# testboard_chip1.net
KiCad netlist of a schematic drawn in Altium Designer
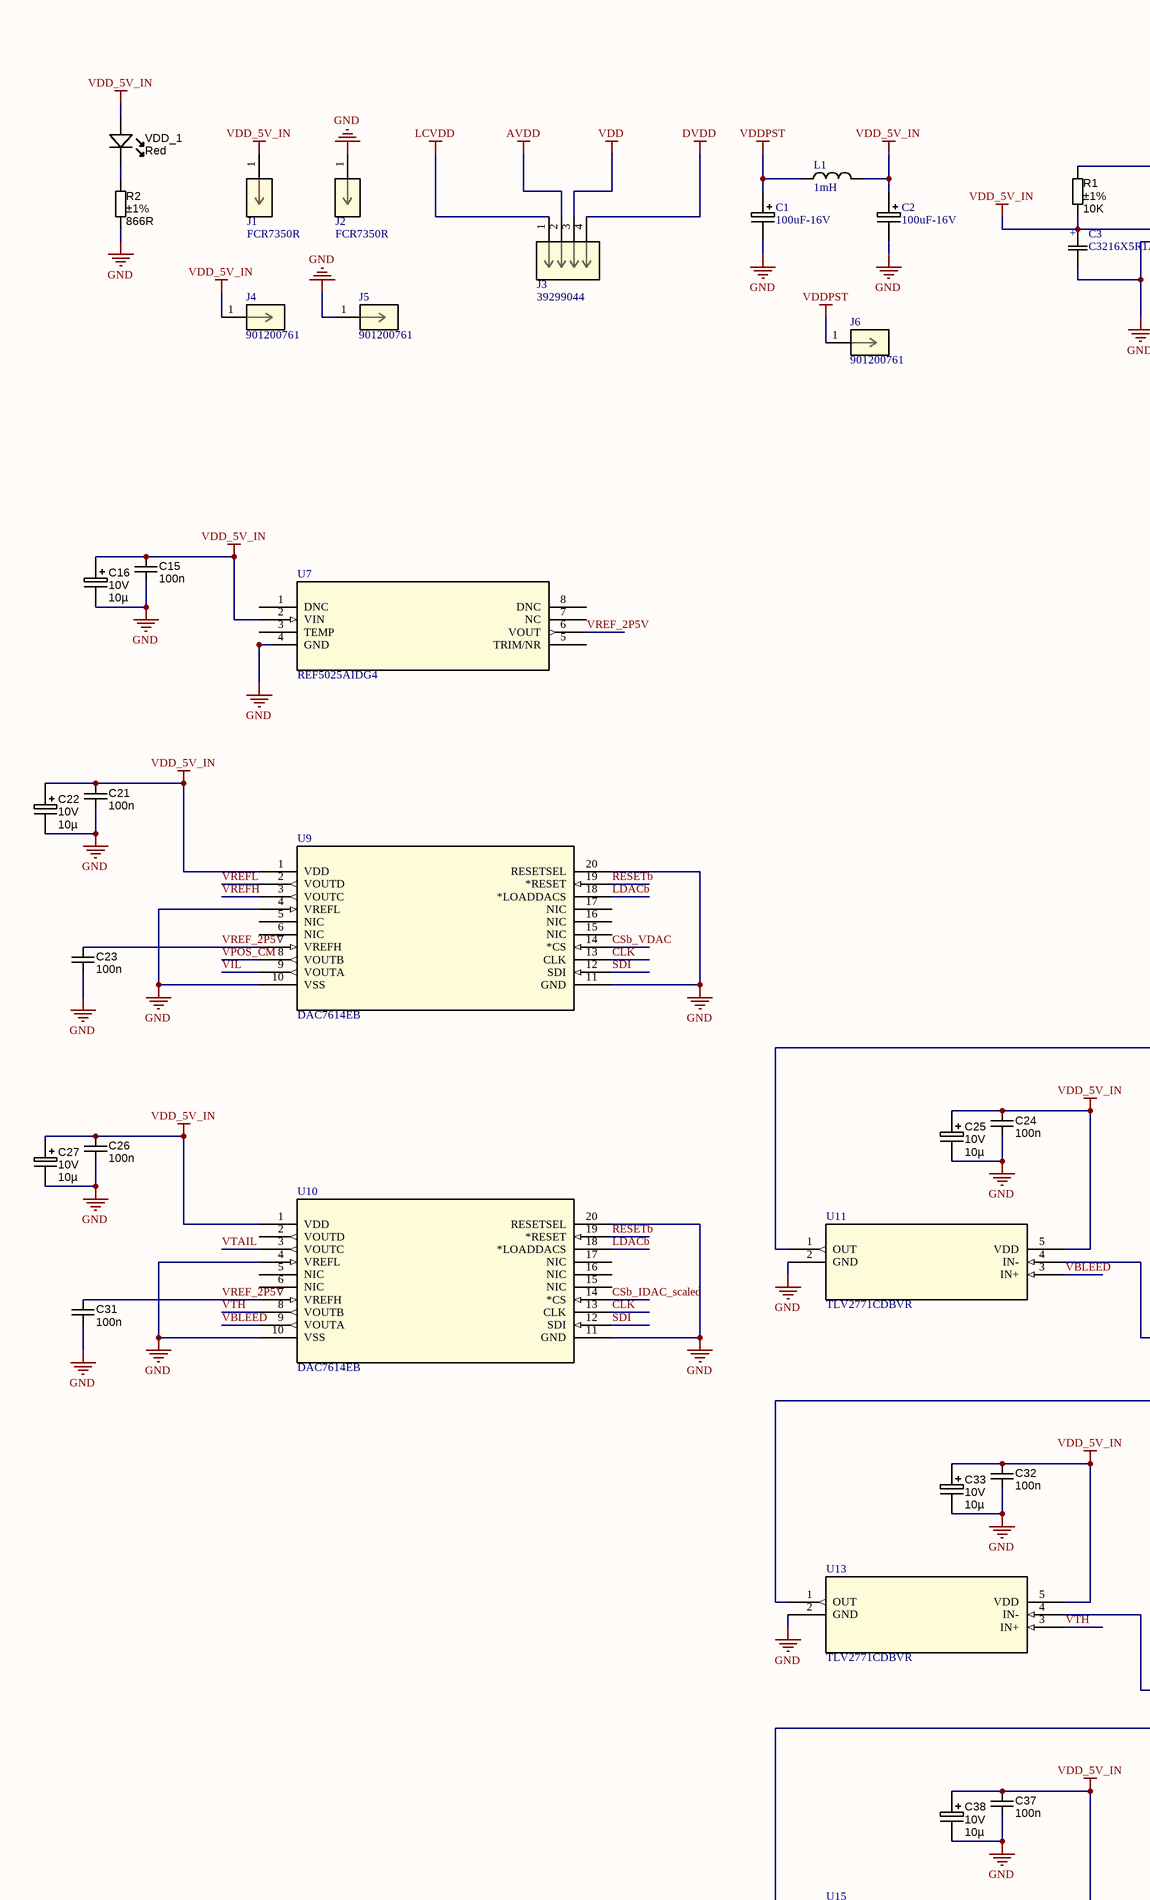
[diagram p0: testboard_chip1.SchDoc, top left]
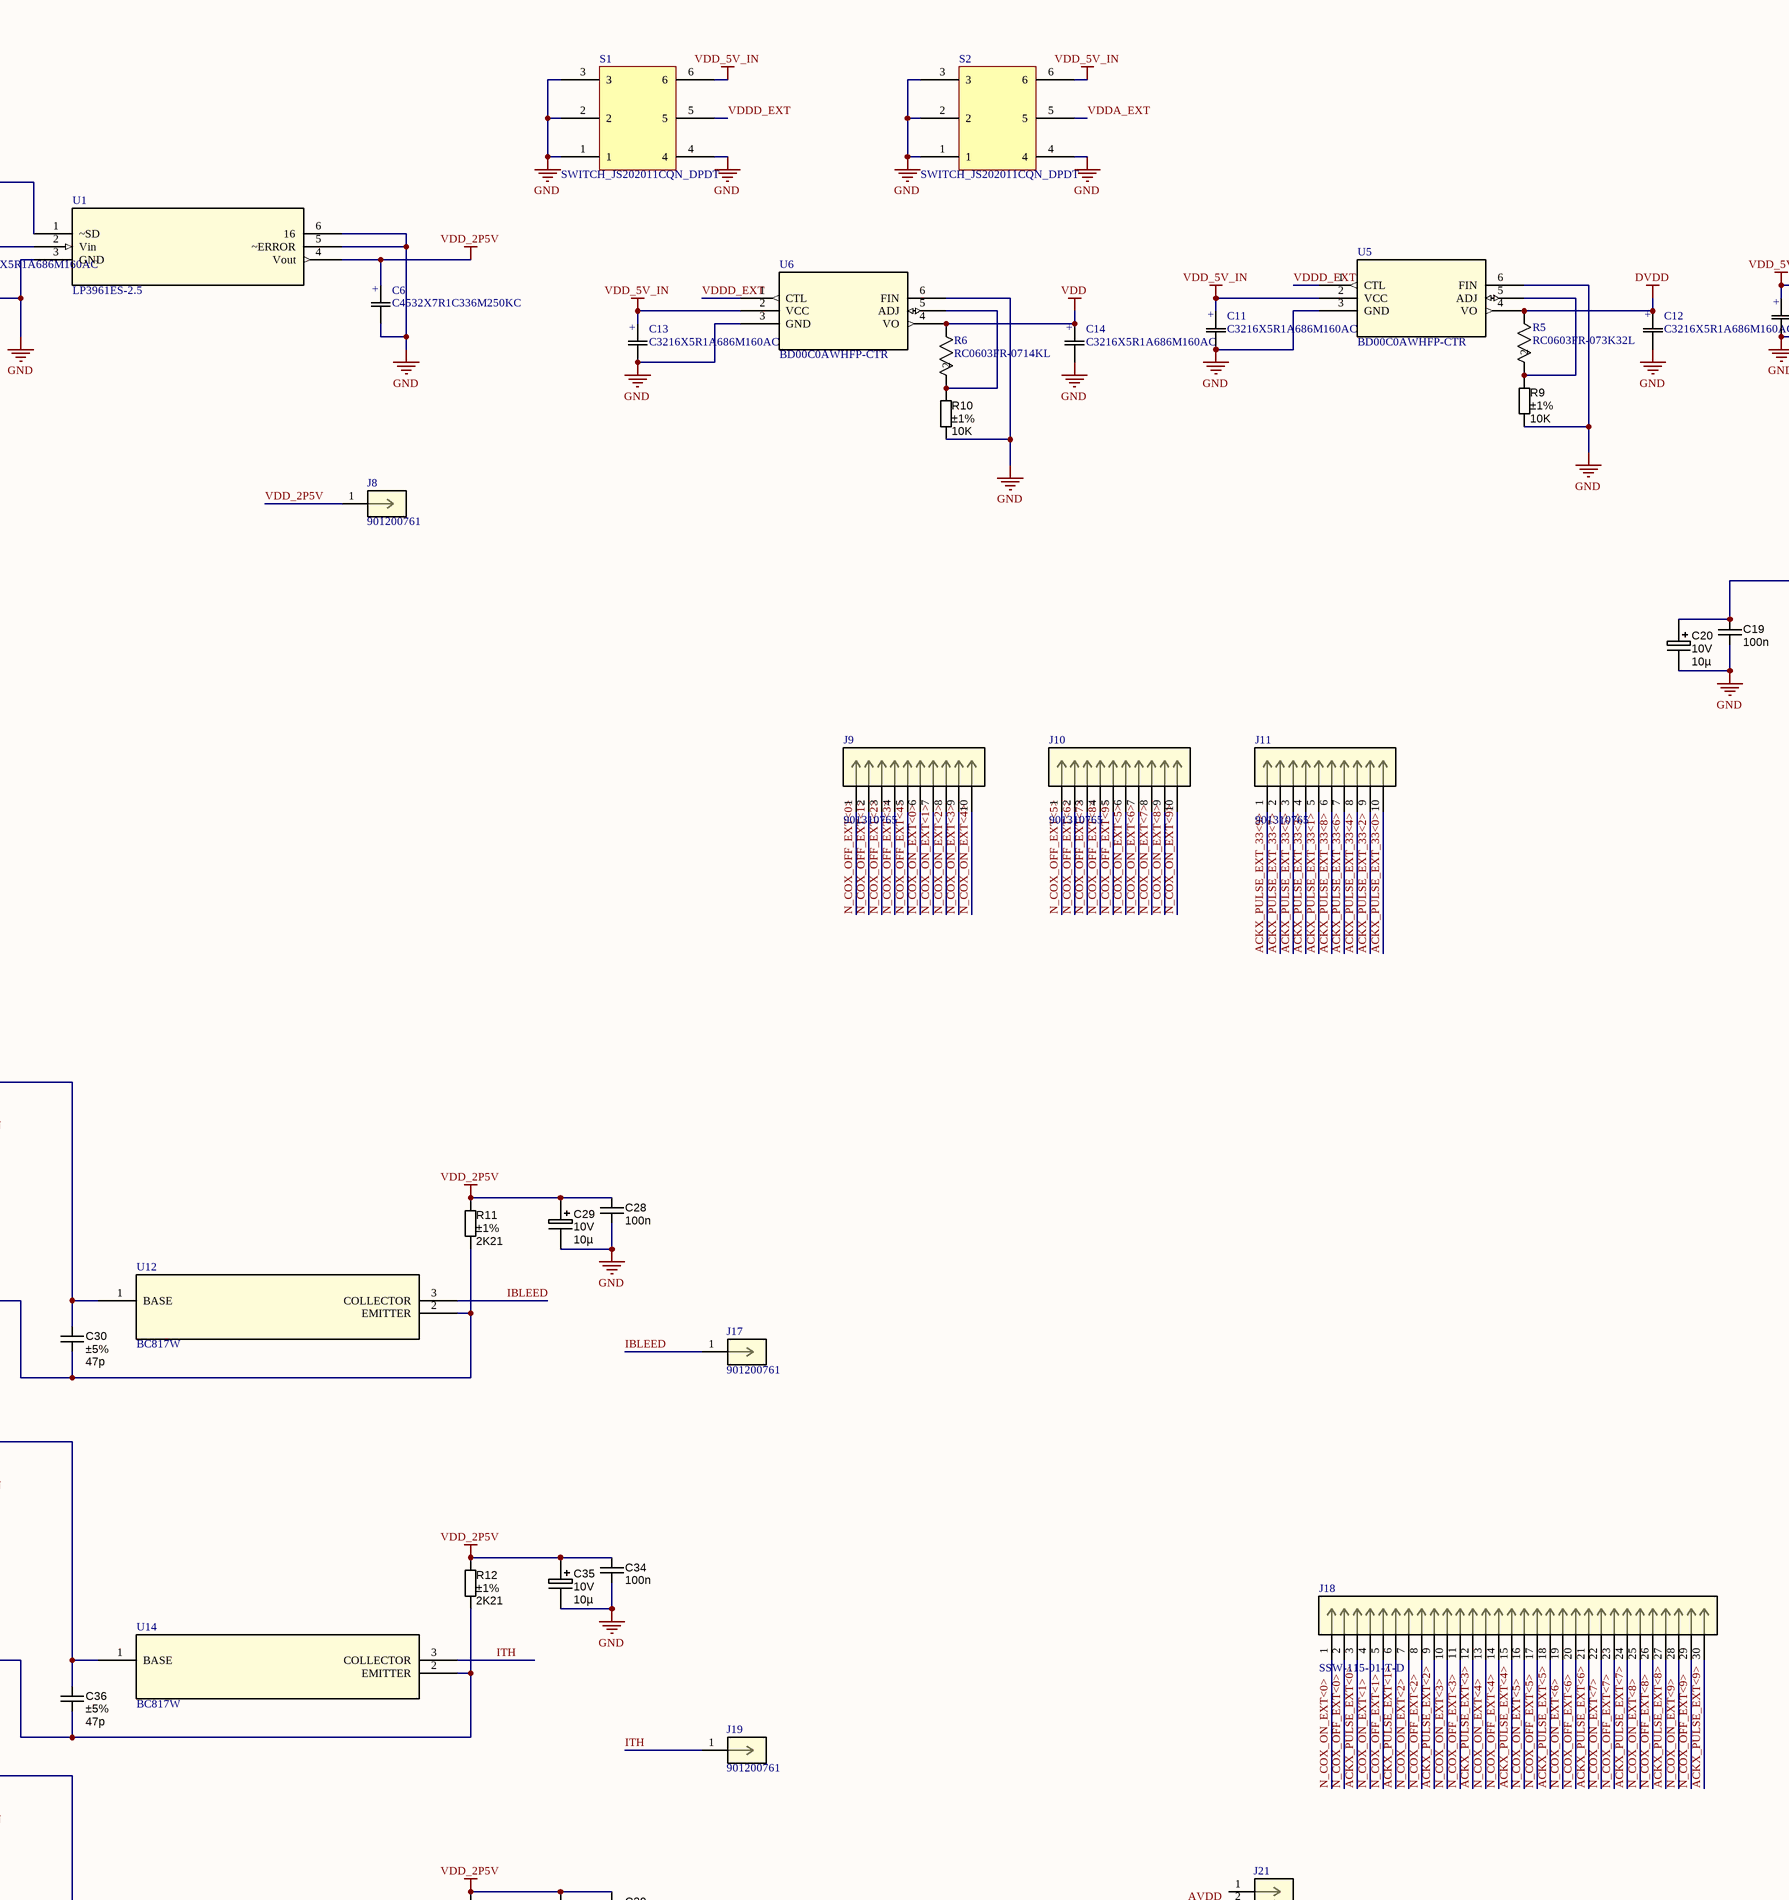
[diagram p1: testboard_chip1.SchDoc, top middle]
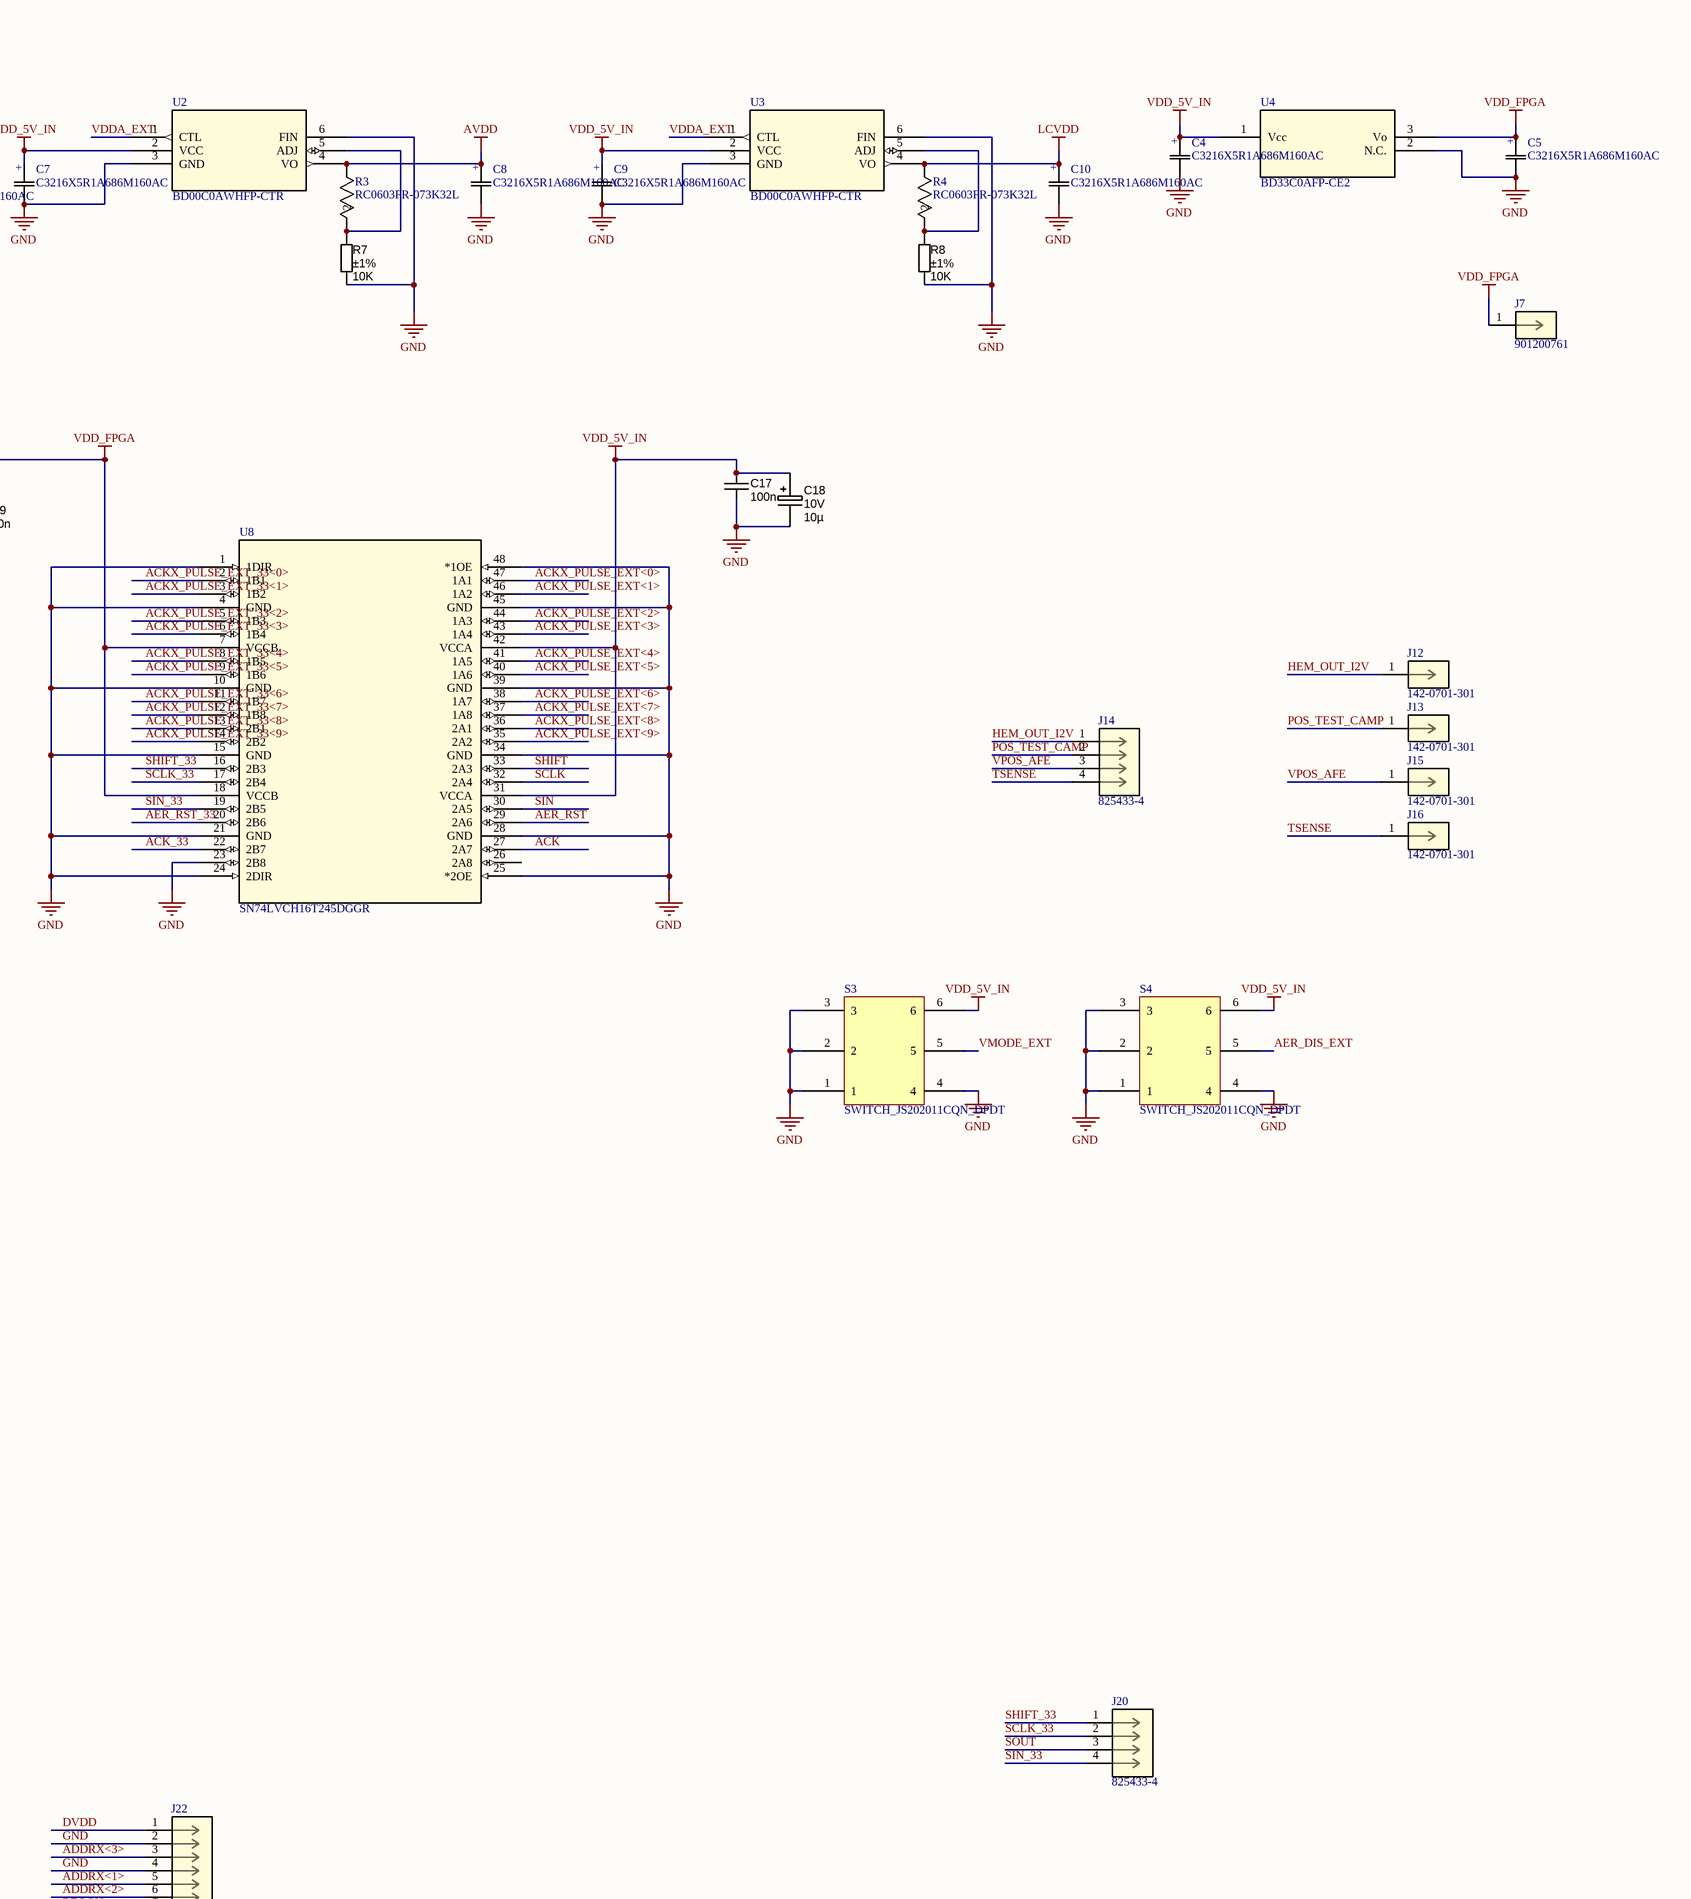
[diagram p2: testboard_chip1.SchDoc, top right]
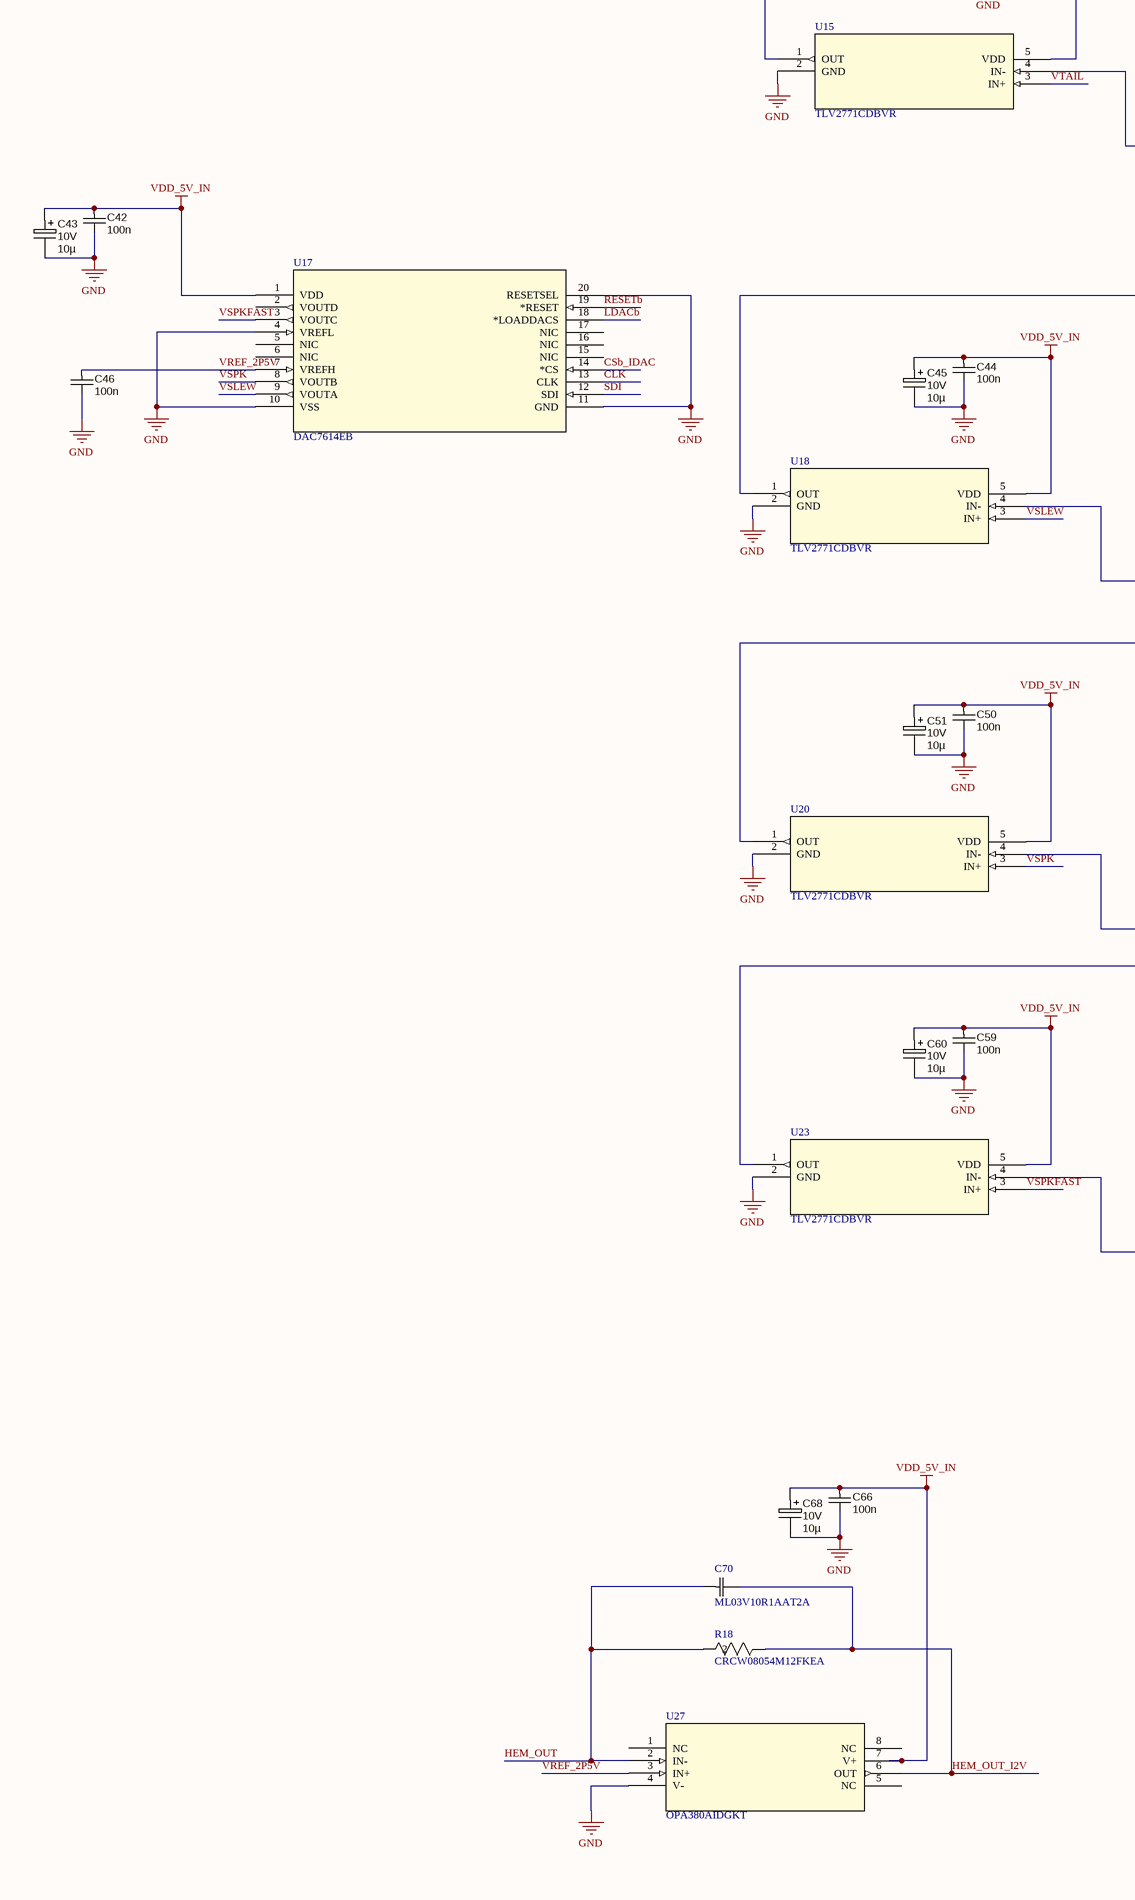
[diagram p3: testboard_chip1.SchDoc, bottom left]
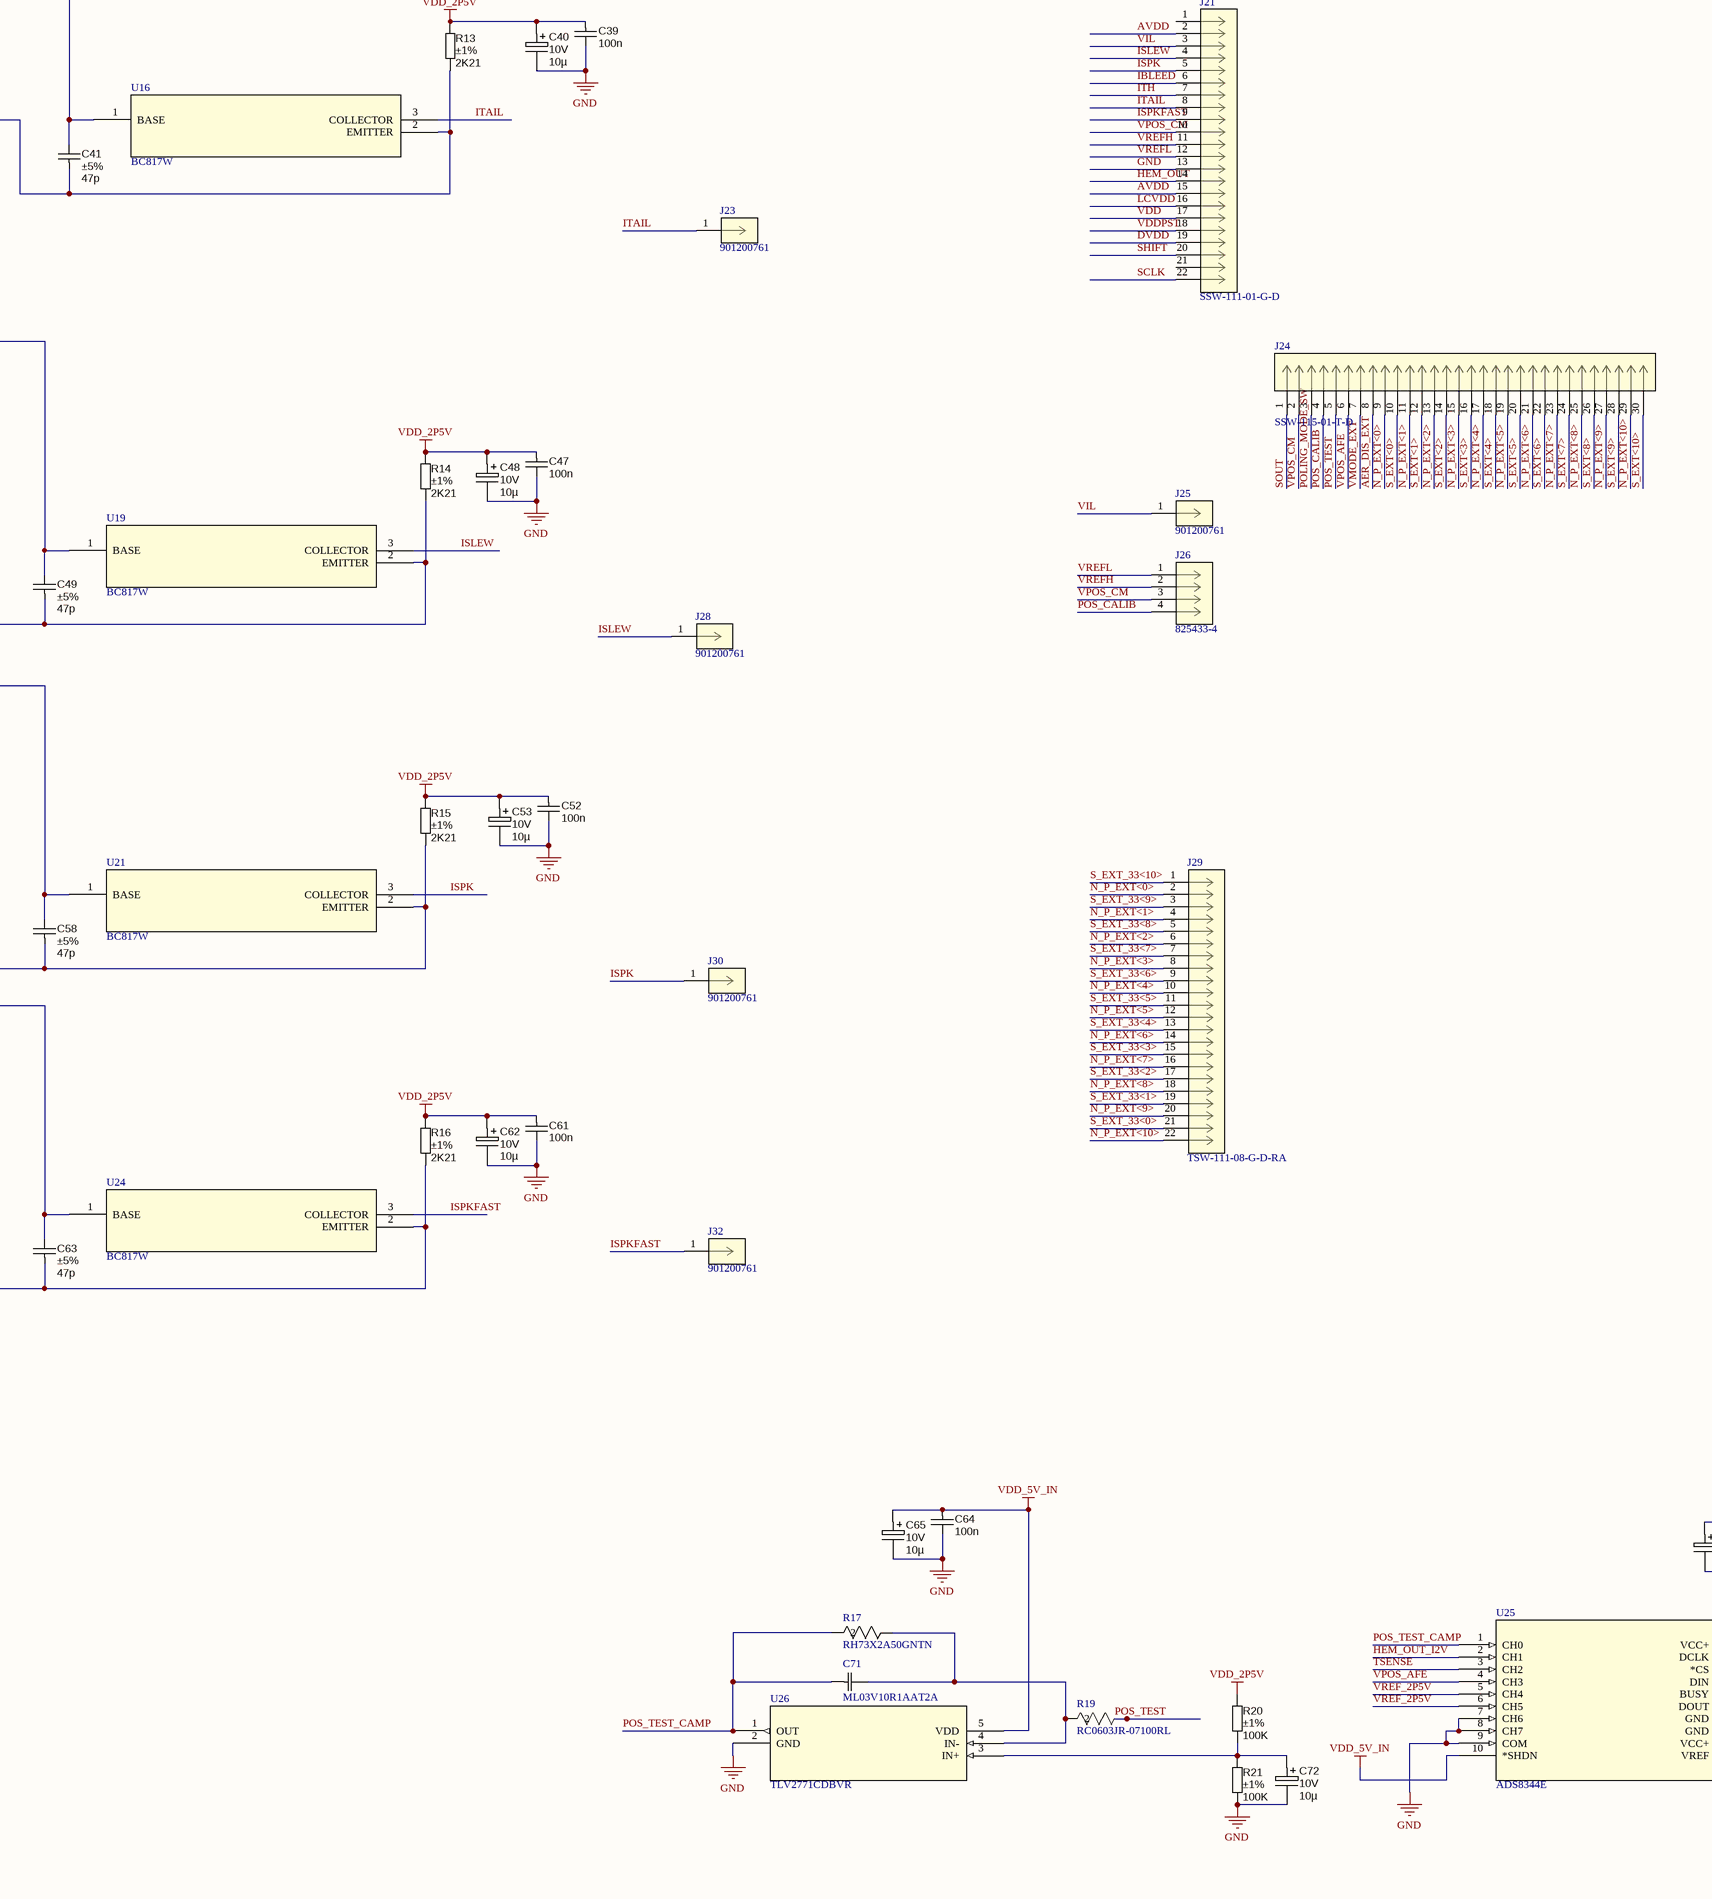
[diagram p4: testboard_chip1.SchDoc, bottom middle]
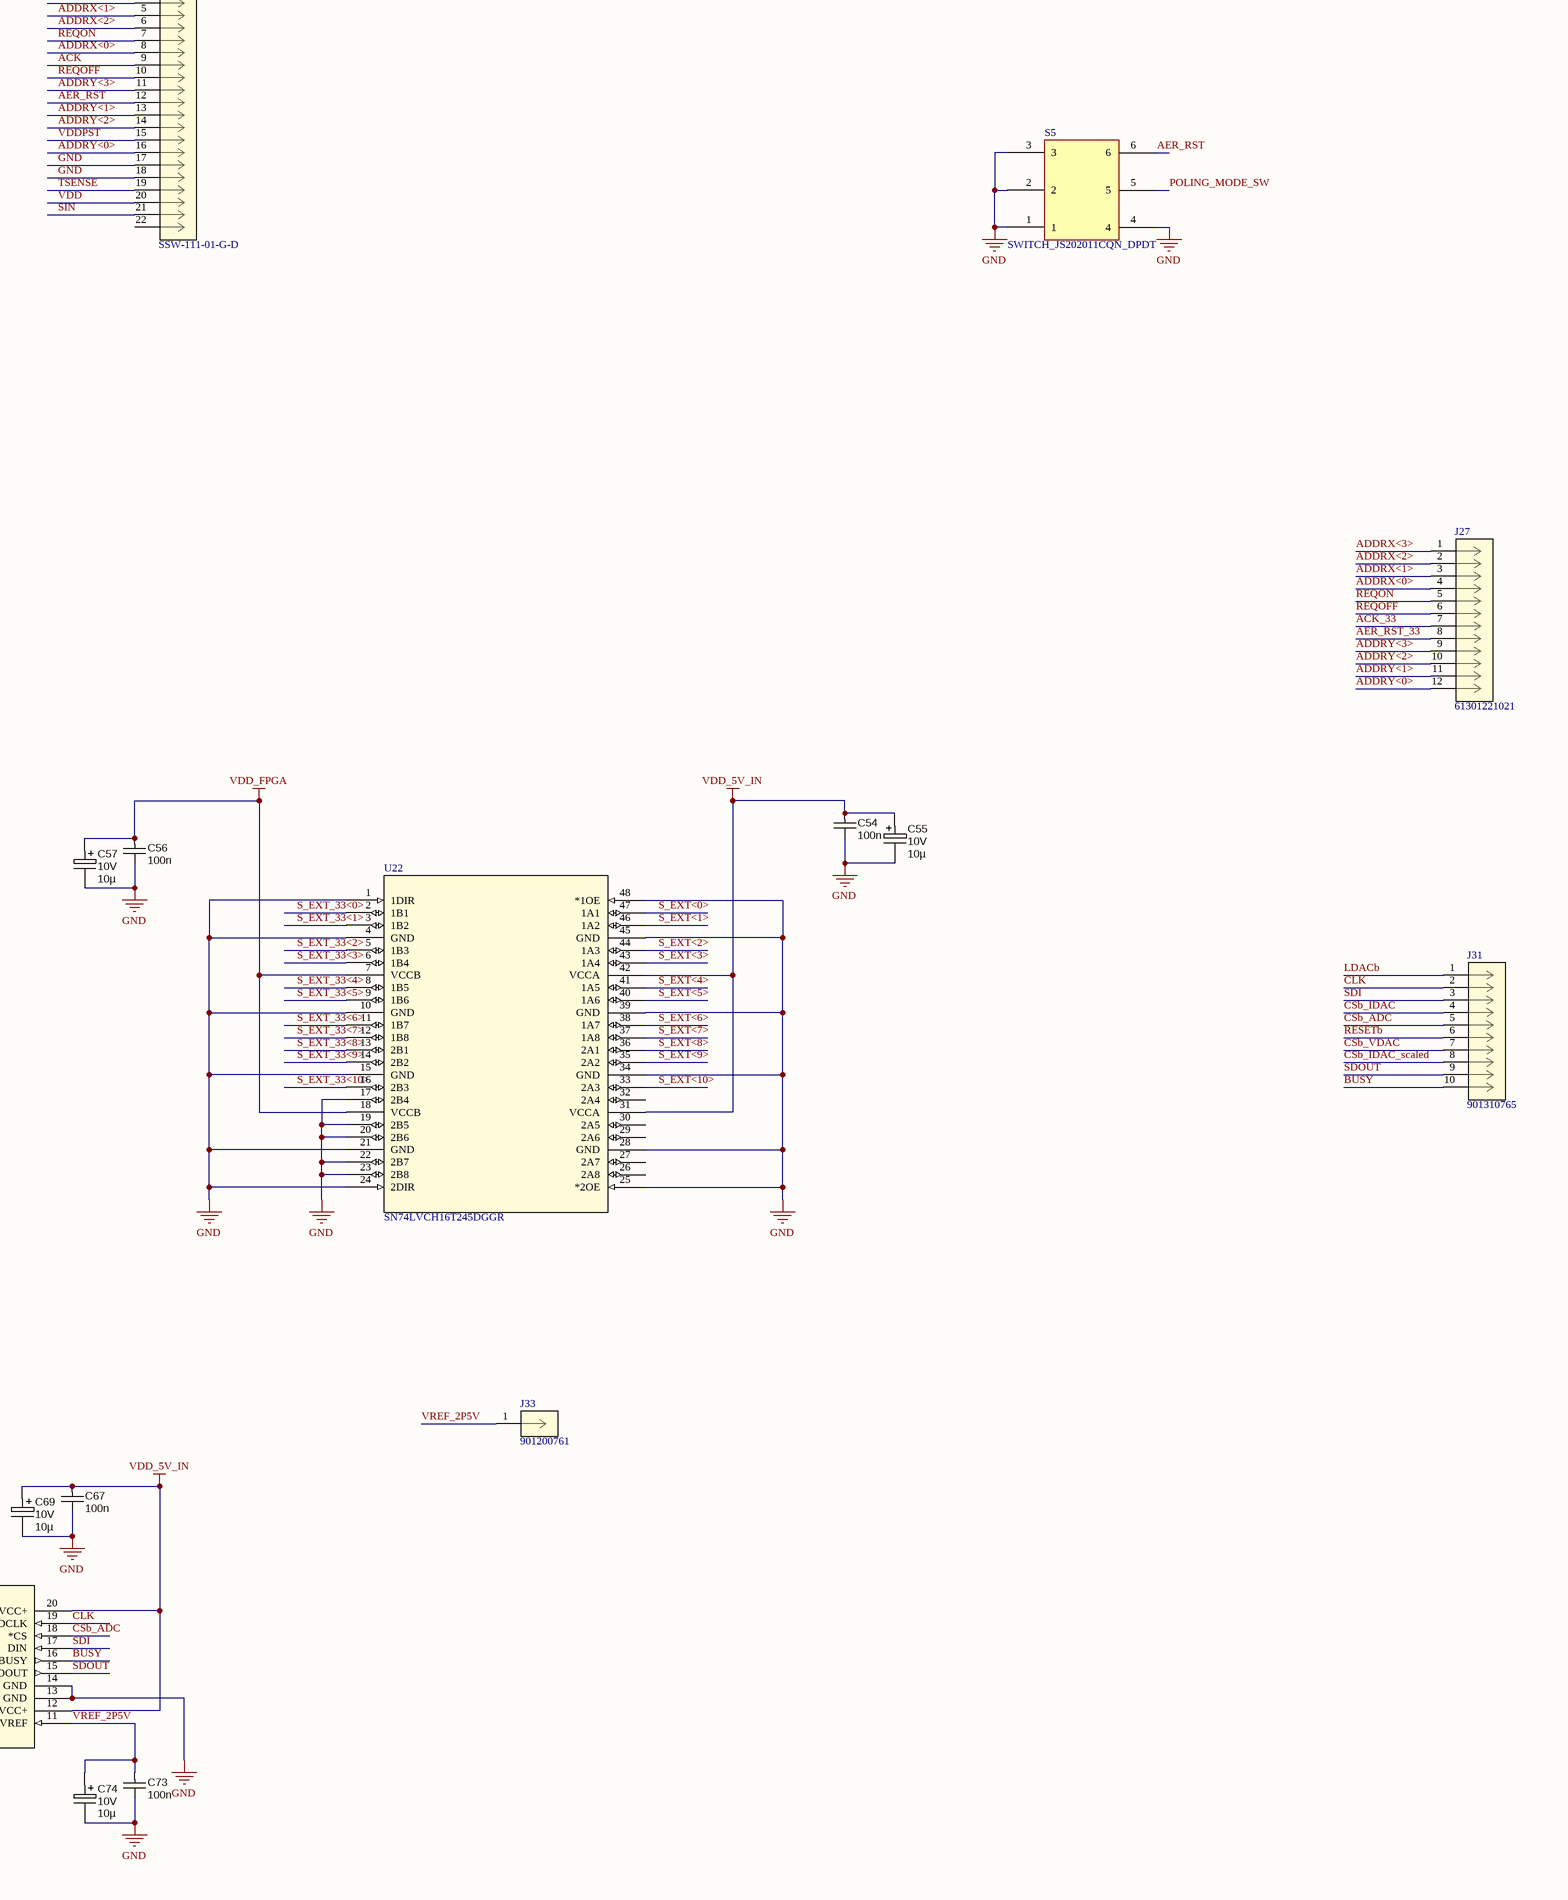
[diagram p5: testboard_chip1.SchDoc, bottom right]

(export (version "E")
  (design (tool "Eeschema 10.0.6"))
  (components
    (comp (ref "C1")
      (value "100uF-16V")
      (footprint "PANACAP-D-GENERIC")
      (description "GENERIC CAPACITOR POLARISED")
      (libsource (lib "analogboard_v2") (part "PANACAP-100UF-16V-FK"))
    )
    (comp (ref "C2")
      (value "100uF-16V")
      (footprint "PANACAP-D-GENERIC")
      (description "GENERIC CAPACITOR POLARISED")
      (libsource (lib "analogboard_v2") (part "PANACAP-100UF-16V-FK"))
    )
    (comp (ref "C3")
      (value "C3216X5R1A686M160AC")
      (footprint "CAP_3216_TDK")
      (description "No Description Available")
      (fields (field (name "COPYRIGHT") "Copyright (C) 2022 Ultra Librarian. All rights reserved."))
      (libsource (lib "C3216X5R1A686M160AC") (part "C3216X5R1A686M160AC"))
    )
    (comp (ref "C4")
      (value "C3216X5R1A686M160AC")
      (footprint "CAP_3216_TDK")
      (description "No Description Available")
      (fields (field (name "COPYRIGHT") "Copyright (C) 2022 Ultra Librarian. All rights reserved."))
      (libsource (lib "C3216X5R1A686M160AC") (part "C3216X5R1A686M160AC"))
    )
    (comp (ref "C5")
      (value "C3216X5R1A686M160AC")
      (footprint "CAP_3216_TDK")
      (description "No Description Available")
      (fields (field (name "COPYRIGHT") "Copyright (C) 2022 Ultra Librarian. All rights reserved."))
      (libsource (lib "C3216X5R1A686M160AC") (part "C3216X5R1A686M160AC"))
    )
    (comp (ref "C6")
      (value "C4532X7R1C336M250KC")
      (footprint "CAP_4532_TDK")
      (description "No Description Available")
      (fields (field (name "COPYRIGHT") "Copyright (C) 2022 Ultra Librarian. All rights reserved."))
      (libsource (lib "C4532X7R1C336M250KC") (part "C4532X7R1C336M250KC"))
    )
    (comp (ref "C7")
      (value "C3216X5R1A686M160AC")
      (footprint "CAP_3216_TDK")
      (description "No Description Available")
      (fields (field (name "COPYRIGHT") "Copyright (C) 2022 Ultra Librarian. All rights reserved."))
      (libsource (lib "C3216X5R1A686M160AC") (part "C3216X5R1A686M160AC"))
    )
    (comp (ref "C8")
      (value "C3216X5R1A686M160AC")
      (footprint "CAP_3216_TDK")
      (description "No Description Available")
      (fields (field (name "COPYRIGHT") "Copyright (C) 2022 Ultra Librarian. All rights reserved."))
      (libsource (lib "C3216X5R1A686M160AC") (part "C3216X5R1A686M160AC"))
    )
    (comp (ref "C9")
      (value "C3216X5R1A686M160AC")
      (footprint "CAP_3216_TDK")
      (description "No Description Available")
      (fields (field (name "COPYRIGHT") "Copyright (C) 2022 Ultra Librarian. All rights reserved."))
      (libsource (lib "C3216X5R1A686M160AC") (part "C3216X5R1A686M160AC"))
    )
    (comp (ref "C10")
      (value "C3216X5R1A686M160AC")
      (footprint "CAP_3216_TDK")
      (description "No Description Available")
      (fields (field (name "COPYRIGHT") "Copyright (C) 2022 Ultra Librarian. All rights reserved."))
      (libsource (lib "C3216X5R1A686M160AC") (part "C3216X5R1A686M160AC"))
    )
    (comp (ref "C11")
      (value "C3216X5R1A686M160AC")
      (footprint "CAP_3216_TDK")
      (description "No Description Available")
      (fields (field (name "COPYRIGHT") "Copyright (C) 2022 Ultra Librarian. All rights reserved."))
      (libsource (lib "C3216X5R1A686M160AC") (part "C3216X5R1A686M160AC"))
    )
    (comp (ref "C12")
      (value "C3216X5R1A686M160AC")
      (footprint "CAP_3216_TDK")
      (description "No Description Available")
      (fields (field (name "COPYRIGHT") "Copyright (C) 2022 Ultra Librarian. All rights reserved."))
      (libsource (lib "C3216X5R1A686M160AC") (part "C3216X5R1A686M160AC"))
    )
    (comp (ref "C13")
      (value "C3216X5R1A686M160AC")
      (footprint "CAP_3216_TDK")
      (description "No Description Available")
      (fields (field (name "COPYRIGHT") "Copyright (C) 2022 Ultra Librarian. All rights reserved."))
      (libsource (lib "C3216X5R1A686M160AC") (part "C3216X5R1A686M160AC"))
    )
    (comp (ref "C14")
      (value "C3216X5R1A686M160AC")
      (footprint "CAP_3216_TDK")
      (description "No Description Available")
      (fields (field (name "COPYRIGHT") "Copyright (C) 2022 Ultra Librarian. All rights reserved."))
      (libsource (lib "C3216X5R1A686M160AC") (part "C3216X5R1A686M160AC"))
    )
    (comp (ref "C15")
      (value "100n")
      (footprint "CAPC1608N")
      (description "Capacitor SMD Cer 100nF 10% 50V X7R 0603")
      (fields (field (name "TOLERANCE") "±10%") (field (name "Comment") "approved sub OK"))
      (libsource (lib "PBL - Capacitors") (part "CAPC_100n_0603"))
    )
    (comp (ref "C16")
      (value "10µ")
      (footprint "CAPMP2012X150USR")
      (description "Capacitor SMD Tantalum 10uF 20% 10V 0805")
      (fields (field (name "TOLERANCE") "±20%") (field (name "RATINGS") "10V"))
      (libsource (lib "PBL - Capacitors") (part "CAPT_10u_0805_10V"))
    )
    (comp (ref "C17")
      (value "100n")
      (footprint "CAPC1608N")
      (description "Capacitor SMD Cer 100nF 10% 50V X7R 0603")
      (fields (field (name "TOLERANCE") "±10%") (field (name "Comment") "approved sub OK"))
      (libsource (lib "PBL - Capacitors") (part "CAPC_100n_0603"))
    )
    (comp (ref "C18")
      (value "10µ")
      (footprint "CAPMP2012X150USR")
      (description "Capacitor SMD Tantalum 10uF 20% 10V 0805")
      (fields (field (name "TOLERANCE") "±20%") (field (name "RATINGS") "10V"))
      (libsource (lib "PBL - Capacitors") (part "CAPT_10u_0805_10V"))
    )
    (comp (ref "C19")
      (value "100n")
      (footprint "CAPC1608N")
      (description "Capacitor SMD Cer 100nF 10% 50V X7R 0603")
      (fields (field (name "TOLERANCE") "±10%") (field (name "Comment") "approved sub OK"))
      (libsource (lib "PBL - Capacitors") (part "CAPC_100n_0603"))
    )
    (comp (ref "C20")
      (value "10µ")
      (footprint "CAPMP2012X150USR")
      (description "Capacitor SMD Tantalum 10uF 20% 10V 0805")
      (fields (field (name "TOLERANCE") "±20%") (field (name "RATINGS") "10V"))
      (libsource (lib "PBL - Capacitors") (part "CAPT_10u_0805_10V"))
    )
    (comp (ref "C21")
      (value "100n")
      (footprint "CAPC1608N")
      (description "Capacitor SMD Cer 100nF 10% 50V X7R 0603")
      (fields (field (name "TOLERANCE") "±10%") (field (name "Comment") "approved sub OK"))
      (libsource (lib "PBL - Capacitors") (part "CAPC_100n_0603"))
    )
    (comp (ref "C22")
      (value "10µ")
      (footprint "CAPMP2012X150USR")
      (description "Capacitor SMD Tantalum 10uF 20% 10V 0805")
      (fields (field (name "TOLERANCE") "±20%") (field (name "RATINGS") "10V"))
      (libsource (lib "PBL - Capacitors") (part "CAPT_10u_0805_10V"))
    )
    (comp (ref "C23")
      (value "100n")
      (footprint "CAPC1608N")
      (description "Capacitor SMD Cer 100nF 10% 50V X7R 0603")
      (fields (field (name "TOLERANCE") "±10%") (field (name "Comment") "approved sub OK"))
      (libsource (lib "PBL - Capacitors") (part "CAPC_100n_0603"))
    )
    (comp (ref "C24")
      (value "100n")
      (footprint "CAPC1608N")
      (description "Capacitor SMD Cer 100nF 10% 50V X7R 0603")
      (fields (field (name "TOLERANCE") "±10%") (field (name "Comment") "approved sub OK"))
      (libsource (lib "PBL - Capacitors") (part "CAPC_100n_0603"))
    )
    (comp (ref "C25")
      (value "10µ")
      (footprint "CAPMP2012X150USR")
      (description "Capacitor SMD Tantalum 10uF 20% 10V 0805")
      (fields (field (name "TOLERANCE") "±20%") (field (name "RATINGS") "10V"))
      (libsource (lib "PBL - Capacitors") (part "CAPT_10u_0805_10V"))
    )
    (comp (ref "C26")
      (value "100n")
      (footprint "CAPC1608N")
      (description "Capacitor SMD Cer 100nF 10% 50V X7R 0603")
      (fields (field (name "TOLERANCE") "±10%") (field (name "Comment") "approved sub OK"))
      (libsource (lib "PBL - Capacitors") (part "CAPC_100n_0603"))
    )
    (comp (ref "C27")
      (value "10µ")
      (footprint "CAPMP2012X150USR")
      (description "Capacitor SMD Tantalum 10uF 20% 10V 0805")
      (fields (field (name "TOLERANCE") "±20%") (field (name "RATINGS") "10V"))
      (libsource (lib "PBL - Capacitors") (part "CAPT_10u_0805_10V"))
    )
    (comp (ref "C28")
      (value "100n")
      (footprint "CAPC1608N")
      (description "Capacitor SMD Cer 100nF 10% 50V X7R 0603")
      (fields (field (name "TOLERANCE") "±10%") (field (name "Comment") "approved sub OK"))
      (libsource (lib "PBL - Capacitors") (part "CAPC_100n_0603"))
    )
    (comp (ref "C29")
      (value "10µ")
      (footprint "CAPMP2012X150USR")
      (description "Capacitor SMD Tantalum 10uF 20% 10V 0805")
      (fields (field (name "TOLERANCE") "±20%") (field (name "RATINGS") "10V"))
      (libsource (lib "PBL - Capacitors") (part "CAPT_10u_0805_10V"))
    )
    (comp (ref "C30")
      (value "47p")
      (footprint "CAPC1608N")
      (description "Capacitor SMD Cer 47pF 0603")
      (fields (field (name "TOLERANCE") "±5%"))
      (libsource (lib "MB - Misc") (part "CAPC_47p_0603"))
    )
    (comp (ref "C31")
      (value "100n")
      (footprint "CAPC1608N")
      (description "Capacitor SMD Cer 100nF 10% 50V X7R 0603")
      (fields (field (name "TOLERANCE") "±10%") (field (name "Comment") "approved sub OK"))
      (libsource (lib "PBL - Capacitors") (part "CAPC_100n_0603"))
    )
    (comp (ref "C32")
      (value "100n")
      (footprint "CAPC1608N")
      (description "Capacitor SMD Cer 100nF 10% 50V X7R 0603")
      (fields (field (name "TOLERANCE") "±10%") (field (name "Comment") "approved sub OK"))
      (libsource (lib "PBL - Capacitors") (part "CAPC_100n_0603"))
    )
    (comp (ref "C33")
      (value "10µ")
      (footprint "CAPMP2012X150USR")
      (description "Capacitor SMD Tantalum 10uF 20% 10V 0805")
      (fields (field (name "TOLERANCE") "±20%") (field (name "RATINGS") "10V"))
      (libsource (lib "PBL - Capacitors") (part "CAPT_10u_0805_10V"))
    )
    (comp (ref "C34")
      (value "100n")
      (footprint "CAPC1608N")
      (description "Capacitor SMD Cer 100nF 10% 50V X7R 0603")
      (fields (field (name "TOLERANCE") "±10%") (field (name "Comment") "approved sub OK"))
      (libsource (lib "PBL - Capacitors") (part "CAPC_100n_0603"))
    )
    (comp (ref "C35")
      (value "10µ")
      (footprint "CAPMP2012X150USR")
      (description "Capacitor SMD Tantalum 10uF 20% 10V 0805")
      (fields (field (name "TOLERANCE") "±20%") (field (name "RATINGS") "10V"))
      (libsource (lib "PBL - Capacitors") (part "CAPT_10u_0805_10V"))
    )
    (comp (ref "C36")
      (value "47p")
      (footprint "CAPC1608N")
      (description "Capacitor SMD Cer 47pF 0603")
      (fields (field (name "TOLERANCE") "±5%"))
      (libsource (lib "MB - Misc") (part "CAPC_47p_0603"))
    )
    (comp (ref "C37")
      (value "100n")
      (footprint "CAPC1608N")
      (description "Capacitor SMD Cer 100nF 10% 50V X7R 0603")
      (fields (field (name "TOLERANCE") "±10%") (field (name "Comment") "approved sub OK"))
      (libsource (lib "PBL - Capacitors") (part "CAPC_100n_0603"))
    )
    (comp (ref "C38")
      (value "10µ")
      (footprint "CAPMP2012X150USR")
      (description "Capacitor SMD Tantalum 10uF 20% 10V 0805")
      (fields (field (name "TOLERANCE") "±20%") (field (name "RATINGS") "10V"))
      (libsource (lib "PBL - Capacitors") (part "CAPT_10u_0805_10V"))
    )
    (comp (ref "C39")
      (value "100n")
      (footprint "CAPC1608N")
      (description "Capacitor SMD Cer 100nF 10% 50V X7R 0603")
      (fields (field (name "TOLERANCE") "±10%") (field (name "Comment") "approved sub OK"))
      (libsource (lib "PBL - Capacitors") (part "CAPC_100n_0603"))
    )
    (comp (ref "C40")
      (value "10µ")
      (footprint "CAPMP2012X150USR")
      (description "Capacitor SMD Tantalum 10uF 20% 10V 0805")
      (fields (field (name "TOLERANCE") "±20%") (field (name "RATINGS") "10V"))
      (libsource (lib "PBL - Capacitors") (part "CAPT_10u_0805_10V"))
    )
    (comp (ref "C41")
      (value "47p")
      (footprint "CAPC1608N")
      (description "Capacitor SMD Cer 47pF 0603")
      (fields (field (name "TOLERANCE") "±5%"))
      (libsource (lib "MB - Misc") (part "CAPC_47p_0603"))
    )
    (comp (ref "C42")
      (value "100n")
      (footprint "CAPC1608N")
      (description "Capacitor SMD Cer 100nF 10% 50V X7R 0603")
      (fields (field (name "TOLERANCE") "±10%") (field (name "Comment") "approved sub OK"))
      (libsource (lib "PBL - Capacitors") (part "CAPC_100n_0603"))
    )
    (comp (ref "C43")
      (value "10µ")
      (footprint "CAPMP2012X150USR")
      (description "Capacitor SMD Tantalum 10uF 20% 10V 0805")
      (fields (field (name "TOLERANCE") "±20%") (field (name "RATINGS") "10V"))
      (libsource (lib "PBL - Capacitors") (part "CAPT_10u_0805_10V"))
    )
    (comp (ref "C44")
      (value "100n")
      (footprint "CAPC1608N")
      (description "Capacitor SMD Cer 100nF 10% 50V X7R 0603")
      (fields (field (name "TOLERANCE") "±10%") (field (name "Comment") "approved sub OK"))
      (libsource (lib "PBL - Capacitors") (part "CAPC_100n_0603"))
    )
    (comp (ref "C45")
      (value "10µ")
      (footprint "CAPMP2012X150USR")
      (description "Capacitor SMD Tantalum 10uF 20% 10V 0805")
      (fields (field (name "TOLERANCE") "±20%") (field (name "RATINGS") "10V"))
      (libsource (lib "PBL - Capacitors") (part "CAPT_10u_0805_10V"))
    )
    (comp (ref "C46")
      (value "100n")
      (footprint "CAPC1608N")
      (description "Capacitor SMD Cer 100nF 10% 50V X7R 0603")
      (fields (field (name "TOLERANCE") "±10%") (field (name "Comment") "approved sub OK"))
      (libsource (lib "PBL - Capacitors") (part "CAPC_100n_0603"))
    )
    (comp (ref "C47")
      (value "100n")
      (footprint "CAPC1608N")
      (description "Capacitor SMD Cer 100nF 10% 50V X7R 0603")
      (fields (field (name "TOLERANCE") "±10%") (field (name "Comment") "approved sub OK"))
      (libsource (lib "PBL - Capacitors") (part "CAPC_100n_0603"))
    )
    (comp (ref "C48")
      (value "10µ")
      (footprint "CAPMP2012X150USR")
      (description "Capacitor SMD Tantalum 10uF 20% 10V 0805")
      (fields (field (name "TOLERANCE") "±20%") (field (name "RATINGS") "10V"))
      (libsource (lib "PBL - Capacitors") (part "CAPT_10u_0805_10V"))
    )
    (comp (ref "C49")
      (value "47p")
      (footprint "CAPC1608N")
      (description "Capacitor SMD Cer 47pF 0603")
      (fields (field (name "TOLERANCE") "±5%"))
      (libsource (lib "MB - Misc") (part "CAPC_47p_0603"))
    )
    (comp (ref "C50")
      (value "100n")
      (footprint "CAPC1608N")
      (description "Capacitor SMD Cer 100nF 10% 50V X7R 0603")
      (fields (field (name "TOLERANCE") "±10%") (field (name "Comment") "approved sub OK"))
      (libsource (lib "PBL - Capacitors") (part "CAPC_100n_0603"))
    )
    (comp (ref "C51")
      (value "10µ")
      (footprint "CAPMP2012X150USR")
      (description "Capacitor SMD Tantalum 10uF 20% 10V 0805")
      (fields (field (name "TOLERANCE") "±20%") (field (name "RATINGS") "10V"))
      (libsource (lib "PBL - Capacitors") (part "CAPT_10u_0805_10V"))
    )
    (comp (ref "C52")
      (value "100n")
      (footprint "CAPC1608N")
      (description "Capacitor SMD Cer 100nF 10% 50V X7R 0603")
      (fields (field (name "TOLERANCE") "±10%") (field (name "Comment") "approved sub OK"))
      (libsource (lib "PBL - Capacitors") (part "CAPC_100n_0603"))
    )
    (comp (ref "C53")
      (value "10µ")
      (footprint "CAPMP2012X150USR")
      (description "Capacitor SMD Tantalum 10uF 20% 10V 0805")
      (fields (field (name "TOLERANCE") "±20%") (field (name "RATINGS") "10V"))
      (libsource (lib "PBL - Capacitors") (part "CAPT_10u_0805_10V"))
    )
    (comp (ref "C54")
      (value "100n")
      (footprint "CAPC1608N")
      (description "Capacitor SMD Cer 100nF 10% 50V X7R 0603")
      (fields (field (name "TOLERANCE") "±10%") (field (name "Comment") "approved sub OK"))
      (libsource (lib "PBL - Capacitors") (part "CAPC_100n_0603"))
    )
    (comp (ref "C55")
      (value "10µ")
      (footprint "CAPMP2012X150USR")
      (description "Capacitor SMD Tantalum 10uF 20% 10V 0805")
      (fields (field (name "TOLERANCE") "±20%") (field (name "RATINGS") "10V"))
      (libsource (lib "PBL - Capacitors") (part "CAPT_10u_0805_10V"))
    )
    (comp (ref "C56")
      (value "100n")
      (footprint "CAPC1608N")
      (description "Capacitor SMD Cer 100nF 10% 50V X7R 0603")
      (fields (field (name "TOLERANCE") "±10%") (field (name "Comment") "approved sub OK"))
      (libsource (lib "PBL - Capacitors") (part "CAPC_100n_0603"))
    )
    (comp (ref "C57")
      (value "10µ")
      (footprint "CAPMP2012X150USR")
      (description "Capacitor SMD Tantalum 10uF 20% 10V 0805")
      (fields (field (name "TOLERANCE") "±20%") (field (name "RATINGS") "10V"))
      (libsource (lib "PBL - Capacitors") (part "CAPT_10u_0805_10V"))
    )
    (comp (ref "C58")
      (value "47p")
      (footprint "CAPC1608N")
      (description "Capacitor SMD Cer 47pF 0603")
      (fields (field (name "TOLERANCE") "±5%"))
      (libsource (lib "MB - Misc") (part "CAPC_47p_0603"))
    )
    (comp (ref "C59")
      (value "100n")
      (footprint "CAPC1608N")
      (description "Capacitor SMD Cer 100nF 10% 50V X7R 0603")
      (fields (field (name "TOLERANCE") "±10%") (field (name "Comment") "approved sub OK"))
      (libsource (lib "PBL - Capacitors") (part "CAPC_100n_0603"))
    )
    (comp (ref "C60")
      (value "10µ")
      (footprint "CAPMP2012X150USR")
      (description "Capacitor SMD Tantalum 10uF 20% 10V 0805")
      (fields (field (name "TOLERANCE") "±20%") (field (name "RATINGS") "10V"))
      (libsource (lib "PBL - Capacitors") (part "CAPT_10u_0805_10V"))
    )
    (comp (ref "C61")
      (value "100n")
      (footprint "CAPC1608N")
      (description "Capacitor SMD Cer 100nF 10% 50V X7R 0603")
      (fields (field (name "TOLERANCE") "±10%") (field (name "Comment") "approved sub OK"))
      (libsource (lib "PBL - Capacitors") (part "CAPC_100n_0603"))
    )
    (comp (ref "C62")
      (value "10µ")
      (footprint "CAPMP2012X150USR")
      (description "Capacitor SMD Tantalum 10uF 20% 10V 0805")
      (fields (field (name "TOLERANCE") "±20%") (field (name "RATINGS") "10V"))
      (libsource (lib "PBL - Capacitors") (part "CAPT_10u_0805_10V"))
    )
    (comp (ref "C63")
      (value "47p")
      (footprint "CAPC1608N")
      (description "Capacitor SMD Cer 47pF 0603")
      (fields (field (name "TOLERANCE") "±5%"))
      (libsource (lib "MB - Misc") (part "CAPC_47p_0603"))
    )
    (comp (ref "C64")
      (value "100n")
      (footprint "CAPC1608N")
      (description "Capacitor SMD Cer 100nF 10% 50V X7R 0603")
      (fields (field (name "TOLERANCE") "±10%") (field (name "Comment") "approved sub OK"))
      (libsource (lib "PBL - Capacitors") (part "CAPC_100n_0603"))
    )
    (comp (ref "C65")
      (value "10µ")
      (footprint "CAPMP2012X150USR")
      (description "Capacitor SMD Tantalum 10uF 20% 10V 0805")
      (fields (field (name "TOLERANCE") "±20%") (field (name "RATINGS") "10V"))
      (libsource (lib "PBL - Capacitors") (part "CAPT_10u_0805_10V"))
    )
    (comp (ref "C66")
      (value "100n")
      (footprint "CAPC1608N")
      (description "Capacitor SMD Cer 100nF 10% 50V X7R 0603")
      (fields (field (name "TOLERANCE") "±10%") (field (name "Comment") "approved sub OK"))
      (libsource (lib "PBL - Capacitors") (part "CAPC_100n_0603"))
    )
    (comp (ref "C67")
      (value "100n")
      (footprint "CAPC1608N")
      (description "Capacitor SMD Cer 100nF 10% 50V X7R 0603")
      (fields (field (name "TOLERANCE") "±10%") (field (name "Comment") "approved sub OK"))
      (libsource (lib "PBL - Capacitors") (part "CAPC_100n_0603"))
    )
    (comp (ref "C68")
      (value "10µ")
      (footprint "CAPMP2012X150USR")
      (description "Capacitor SMD Tantalum 10uF 20% 10V 0805")
      (fields (field (name "TOLERANCE") "±20%") (field (name "RATINGS") "10V"))
      (libsource (lib "PBL - Capacitors") (part "CAPT_10u_0805_10V"))
    )
    (comp (ref "C69")
      (value "10µ")
      (footprint "CAPMP2012X150USR")
      (description "Capacitor SMD Tantalum 10uF 20% 10V 0805")
      (fields (field (name "TOLERANCE") "±20%") (field (name "RATINGS") "10V"))
      (libsource (lib "PBL - Capacitors") (part "CAPT_10u_0805_10V"))
    )
    (comp (ref "C70")
      (value "ML03V10R1AAT2A")
      (footprint "CAP_0603_AVX")
      (description "No Description Available")
      (fields (field (name "COPYRIGHT") "Copyright (C) 2022 Ultra Librarian. All rights reserved."))
      (libsource (lib "ML03V10R1AAT2A") (part "ML03V10R1AAT2A"))
    )
    (comp (ref "C71")
      (value "ML03V10R1AAT2A")
      (footprint "CAP_0603_AVX")
      (description "No Description Available")
      (fields (field (name "COPYRIGHT") "Copyright (C) 2022 Ultra Librarian. All rights reserved."))
      (libsource (lib "ML03V10R1AAT2A") (part "ML03V10R1AAT2A"))
    )
    (comp (ref "C72")
      (value "10µ")
      (footprint "CAPMP2012X150USR")
      (description "Capacitor SMD Tantalum 10uF 20% 10V 0805")
      (fields (field (name "TOLERANCE") "±20%") (field (name "RATINGS") "10V"))
      (libsource (lib "PBL - Capacitors") (part "CAPT_10u_0805_10V"))
    )
    (comp (ref "C73")
      (value "100n")
      (footprint "CAPC1608N")
      (description "Capacitor SMD Cer 100nF 10% 50V X7R 0603")
      (fields (field (name "TOLERANCE") "±10%") (field (name "Comment") "approved sub OK"))
      (libsource (lib "PBL - Capacitors") (part "CAPC_100n_0603"))
    )
    (comp (ref "C74")
      (value "10µ")
      (footprint "CAPMP2012X150USR")
      (description "Capacitor SMD Tantalum 10uF 20% 10V 0805")
      (fields (field (name "TOLERANCE") "±20%") (field (name "RATINGS") "10V"))
      (libsource (lib "PBL - Capacitors") (part "CAPT_10u_0805_10V"))
    )
    (comp (ref "J1")
      (value "FCR7350R")
      (footprint "CONN1_FCR7350R_CLF")
      (description "No Description Available")
      (fields (field (name "COPYRIGHT") "Copyright (C) 2022 Ultra Librarian. All rights reserved."))
      (libsource (lib "FCR7350R") (part "FCR7350R"))
    )
    (comp (ref "J2")
      (value "FCR7350R")
      (footprint "CONN1_FCR7350R_CLF")
      (description "No Description Available")
      (fields (field (name "COPYRIGHT") "Copyright (C) 2022 Ultra Librarian. All rights reserved."))
      (libsource (lib "FCR7350B") (part "FCR7350R"))
    )
    (comp (ref "J3")
      (value "39299044")
      (footprint "CON_39299044")
      (description "No Description Available")
      (fields (field (name "COPYRIGHT") "Copyright (C) 2022 Ultra Librarian. All rights reserved."))
      (libsource (lib "39299044") (part "39299044"))
    )
    (comp (ref "J4")
      (value "901200761")
      (footprint "CONN_90120-0761_MOL")
      (description "No Description Available")
      (fields (field (name "COPYRIGHT") "Copyright (C) 2022 Ultra Librarian. All rights reserved."))
      (libsource (lib "901200761") (part "901200761"))
    )
    (comp (ref "J5")
      (value "901200761")
      (footprint "CONN_90120-0761_MOL")
      (description "No Description Available")
      (fields (field (name "COPYRIGHT") "Copyright (C) 2022 Ultra Librarian. All rights reserved."))
      (libsource (lib "901200761") (part "901200761"))
    )
    (comp (ref "J6")
      (value "901200761")
      (footprint "CONN_90120-0761_MOL")
      (description "No Description Available")
      (fields (field (name "COPYRIGHT") "Copyright (C) 2022 Ultra Librarian. All rights reserved."))
      (libsource (lib "901200761") (part "901200761"))
    )
    (comp (ref "J7")
      (value "901200761")
      (footprint "CONN_90120-0761_MOL")
      (description "No Description Available")
      (fields (field (name "COPYRIGHT") "Copyright (C) 2022 Ultra Librarian. All rights reserved."))
      (libsource (lib "901200761") (part "901200761"))
    )
    (comp (ref "J8")
      (value "901200761")
      (footprint "CONN_90120-0761_MOL")
      (description "No Description Available")
      (fields (field (name "COPYRIGHT") "Copyright (C) 2022 Ultra Librarian. All rights reserved."))
      (libsource (lib "901200761") (part "901200761"))
    )
    (comp (ref "J9")
      (value "901310765")
      (footprint "CONN_901310765_MOL")
      (description "No Description Available")
      (fields (field (name "COPYRIGHT") "Copyright (C) 2022 Ultra Librarian. All rights reserved."))
      (libsource (lib "901310765") (part "901310765"))
    )
    (comp (ref "J10")
      (value "901310765")
      (footprint "CONN_901310765_MOL")
      (description "No Description Available")
      (fields (field (name "COPYRIGHT") "Copyright (C) 2022 Ultra Librarian. All rights reserved."))
      (libsource (lib "901310765") (part "901310765"))
    )
    (comp (ref "J11")
      (value "901310765")
      (footprint "CONN_901310765_MOL")
      (description "No Description Available")
      (fields (field (name "COPYRIGHT") "Copyright (C) 2022 Ultra Librarian. All rights reserved."))
      (libsource (lib "901310765") (part "901310765"))
    )
    (comp (ref "J12")
      (value "142-0701-301")
      (footprint "CONN_142-0701-301_CIN")
      (description "No Description Available")
      (fields (field (name "COPYRIGHT") "Copyright (C) 2022 Ultra Librarian. All rights reserved."))
      (libsource (lib "142-0701-301") (part "142-0701-301"))
    )
    (comp (ref "J13")
      (value "142-0701-301")
      (footprint "CONN_142-0701-301_CIN")
      (description "No Description Available")
      (fields (field (name "COPYRIGHT") "Copyright (C) 2022 Ultra Librarian. All rights reserved."))
      (libsource (lib "142-0701-301") (part "142-0701-301"))
    )
    (comp (ref "J14")
      (value "825433-4")
      (footprint "CON4_1X4_P100UM_HDR2_TYC")
      (description "No Description Available")
      (fields (field (name "COPYRIGHT") "Copyright (C) 2022 Ultra Librarian. All rights reserved."))
      (libsource (lib "825433-4") (part "825433-4"))
    )
    (comp (ref "J15")
      (value "142-0701-301")
      (footprint "CONN_142-0701-301_CIN")
      (description "No Description Available")
      (fields (field (name "COPYRIGHT") "Copyright (C) 2022 Ultra Librarian. All rights reserved."))
      (libsource (lib "142-0701-301") (part "142-0701-301"))
    )
    (comp (ref "J16")
      (value "142-0701-301")
      (footprint "CONN_142-0701-301_CIN")
      (description "No Description Available")
      (fields (field (name "COPYRIGHT") "Copyright (C) 2022 Ultra Librarian. All rights reserved."))
      (libsource (lib "142-0701-301") (part "142-0701-301"))
    )
    (comp (ref "J17")
      (value "901200761")
      (footprint "CONN_90120-0761_MOL")
      (description "No Description Available")
      (fields (field (name "COPYRIGHT") "Copyright (C) 2022 Ultra Librarian. All rights reserved."))
      (libsource (lib "901200761") (part "901200761"))
    )
    (comp (ref "J18")
      (value "SSW-115-01-T-D")
      (footprint "CON30_2X15_TU_SSQ")
      (description "No Description Available")
      (fields (field (name "COPYRIGHT") "Copyright (C) 2022 Ultra Librarian. All rights reserved."))
      (libsource (lib "SSW-115-01-T-D") (part "SSW-115-01-T-D"))
    )
    (comp (ref "J19")
      (value "901200761")
      (footprint "CONN_90120-0761_MOL")
      (description "No Description Available")
      (fields (field (name "COPYRIGHT") "Copyright (C) 2022 Ultra Librarian. All rights reserved."))
      (libsource (lib "901200761") (part "901200761"))
    )
    (comp (ref "J20")
      (value "825433-4")
      (footprint "CON4_1X4_P100UM_HDR2_TYC")
      (description "No Description Available")
      (fields (field (name "COPYRIGHT") "Copyright (C) 2022 Ultra Librarian. All rights reserved."))
      (libsource (lib "825433-4") (part "825433-4"))
    )
    (comp (ref "J21")
      (value "SSW-111-01-G-D")
      (footprint "CON23_2X11_TU_SSQ")
      (description "No Description Available")
      (fields (field (name "COPYRIGHT") "Copyright (C) 2022 Ultra Librarian. All rights reserved."))
      (libsource (lib "SSW-111-01-G-D") (part "SSW-111-01-G-D"))
    )
    (comp (ref "J22")
      (value "SSW-111-01-G-D")
      (footprint "CON23_2X11_TU_SSQ")
      (description "No Description Available")
      (fields (field (name "COPYRIGHT") "Copyright (C) 2022 Ultra Librarian. All rights reserved."))
      (libsource (lib "SSW-111-01-G-D") (part "SSW-111-01-G-D"))
    )
    (comp (ref "J23")
      (value "901200761")
      (footprint "CONN_90120-0761_MOL")
      (description "No Description Available")
      (fields (field (name "COPYRIGHT") "Copyright (C) 2022 Ultra Librarian. All rights reserved."))
      (libsource (lib "901200761") (part "901200761"))
    )
    (comp (ref "J24")
      (value "SSW-115-01-T-D")
      (footprint "CON30_2X15_TU_SSQ")
      (description "No Description Available")
      (fields (field (name "COPYRIGHT") "Copyright (C) 2022 Ultra Librarian. All rights reserved."))
      (libsource (lib "SSW-115-01-T-D") (part "SSW-115-01-T-D"))
    )
    (comp (ref "J25")
      (value "901200761")
      (footprint "CONN_90120-0761_MOL")
      (description "No Description Available")
      (fields (field (name "COPYRIGHT") "Copyright (C) 2022 Ultra Librarian. All rights reserved."))
      (libsource (lib "901200761") (part "901200761"))
    )
    (comp (ref "J26")
      (value "825433-4")
      (footprint "CON4_1X4_P100UM_HDR2_TYC")
      (description "No Description Available")
      (fields (field (name "COPYRIGHT") "Copyright (C) 2022 Ultra Librarian. All rights reserved."))
      (libsource (lib "825433-4") (part "825433-4"))
    )
    (comp (ref "J27")
      (value "61301221021")
      (footprint "CONN_61301221021_WRE")
      (description "No Description Available")
      (fields (field (name "COPYRIGHT") "Copyright (C) 2022 Ultra Librarian. All rights reserved."))
      (libsource (lib "61301221021") (part "61301221021"))
    )
    (comp (ref "J28")
      (value "901200761")
      (footprint "CONN_90120-0761_MOL")
      (description "No Description Available")
      (fields (field (name "COPYRIGHT") "Copyright (C) 2022 Ultra Librarian. All rights reserved."))
      (libsource (lib "901200761") (part "901200761"))
    )
    (comp (ref "J29")
      (value "TSW-111-08-G-D-RA")
      (footprint "CON23_2X11_TR_TSW_SAI")
      (description "No Description Available")
      (fields (field (name "COPYRIGHT") "Copyright (C) 2022 Ultra Librarian. All rights reserved."))
      (libsource (lib "TSW-111-08-G-D-RA") (part "TSW-111-08-G-D-RA"))
    )
    (comp (ref "J30")
      (value "901200761")
      (footprint "CONN_90120-0761_MOL")
      (description "No Description Available")
      (fields (field (name "COPYRIGHT") "Copyright (C) 2022 Ultra Librarian. All rights reserved."))
      (libsource (lib "901200761") (part "901200761"))
    )
    (comp (ref "J31")
      (value "901310765")
      (footprint "CONN_901310765_MOL")
      (description "No Description Available")
      (fields (field (name "COPYRIGHT") "Copyright (C) 2022 Ultra Librarian. All rights reserved."))
      (libsource (lib "") (part "901310765_1"))
    )
    (comp (ref "J32")
      (value "901200761")
      (footprint "CONN_90120-0761_MOL")
      (description "No Description Available")
      (fields (field (name "COPYRIGHT") "Copyright (C) 2022 Ultra Librarian. All rights reserved."))
      (libsource (lib "901200761") (part "901200761"))
    )
    (comp (ref "J33")
      (value "901200761")
      (footprint "CONN_90120-0761_MOL")
      (description "No Description Available")
      (fields (field (name "COPYRIGHT") "Copyright (C) 2022 Ultra Librarian. All rights reserved."))
      (libsource (lib "901200761") (part "901200761"))
    )
    (comp (ref "L1")
      (value "1mH")
      (footprint "MCSDRB7032-102MHF")
      (description "1mH 150mA inductor")
      (libsource (lib "MB - Misc") (part "MCSDRB7032-102MHF"))
    )
    (comp (ref "R1")
      (value "10K")
      (footprint "RESC1608N")
      (description "Resistor SMD chip 10k Ohm 0.1W 1% 0603")
      (fields (field (name "TOLERANCE") "±1%") (field (name "Comment") "Thick Film"))
      (libsource (lib "analogboard_v2") (part "RES_10K_0603_1%"))
    )
    (comp (ref "R2")
      (value "866R")
      (footprint "RESC1608N")
      (description "Resistor SMD chip 866 Ohm 0.1W 1% 0603")
      (fields (field (name "TOLERANCE") "±1%") (field (name "Comment") "Thick Film"))
      (libsource (lib "MB - Misc") (part "RES_866R_0603_1%_1"))
    )
    (comp (ref "R3")
      (value "RC0603FR-073K32L")
      (footprint "RC0603N_YAG")
      (description "No Description Available")
      (fields (field (name "COPYRIGHT") "Copyright (C) 2022 Ultra Librarian. All rights reserved."))
      (libsource (lib "RC0603FR-073K32L") (part "RC0603FR-073K32L"))
    )
    (comp (ref "R4")
      (value "RC0603FR-073K32L")
      (footprint "RC0603N_YAG")
      (description "No Description Available")
      (fields (field (name "COPYRIGHT") "Copyright (C) 2022 Ultra Librarian. All rights reserved."))
      (libsource (lib "RC0603FR-073K32L") (part "RC0603FR-073K32L"))
    )
    (comp (ref "R5")
      (value "RC0603FR-073K32L")
      (footprint "RC0603N_YAG")
      (description "No Description Available")
      (fields (field (name "COPYRIGHT") "Copyright (C) 2022 Ultra Librarian. All rights reserved."))
      (libsource (lib "RC0603FR-073K32L") (part "RC0603FR-073K32L"))
    )
    (comp (ref "R6")
      (value "RC0603FR-0714KL")
      (footprint "RC0603N_YAG")
      (description "No Description Available")
      (fields (field (name "COPYRIGHT") "Copyright (C) 2022 Ultra Librarian. All rights reserved."))
      (libsource (lib "RC0603FR-0714KL") (part "RC0603FR-0714KL"))
    )
    (comp (ref "R7")
      (value "10K")
      (footprint "RESC1608N")
      (description "Resistor SMD chip 10k Ohm 0.1W 1% 0603")
      (fields (field (name "TOLERANCE") "±1%") (field (name "Comment") "Thick Film"))
      (libsource (lib "analogboard_v2") (part "RES_10K_0603_1%"))
    )
    (comp (ref "R8")
      (value "10K")
      (footprint "RESC1608N")
      (description "Resistor SMD chip 10k Ohm 0.1W 1% 0603")
      (fields (field (name "TOLERANCE") "±1%") (field (name "Comment") "Thick Film"))
      (libsource (lib "analogboard_v2") (part "RES_10K_0603_1%"))
    )
    (comp (ref "R9")
      (value "10K")
      (footprint "RESC1608N")
      (description "Resistor SMD chip 10k Ohm 0.1W 1% 0603")
      (fields (field (name "TOLERANCE") "±1%") (field (name "Comment") "Thick Film"))
      (libsource (lib "analogboard_v2") (part "RES_10K_0603_1%"))
    )
    (comp (ref "R10")
      (value "10K")
      (footprint "RESC1608N")
      (description "Resistor SMD chip 10k Ohm 0.1W 1% 0603")
      (fields (field (name "TOLERANCE") "±1%") (field (name "Comment") "Thick Film"))
      (libsource (lib "analogboard_v2") (part "RES_10K_0603_1%"))
    )
    (comp (ref "R11")
      (value "2K21")
      (footprint "RESC1608N")
      (description "Resistor SMD chip 2.21k Ohm 0.1W 1% 0603")
      (fields (field (name "TOLERANCE") "±1%") (field (name "Comment") "Thick Film"))
      (libsource (lib "analogboard_v2") (part "RES_2K21_0603_1%"))
    )
    (comp (ref "R12")
      (value "2K21")
      (footprint "RESC1608N")
      (description "Resistor SMD chip 2.21k Ohm 0.1W 1% 0603")
      (fields (field (name "TOLERANCE") "±1%") (field (name "Comment") "Thick Film"))
      (libsource (lib "analogboard_v2") (part "RES_2K21_0603_1%"))
    )
    (comp (ref "R13")
      (value "2K21")
      (footprint "RESC1608N")
      (description "Resistor SMD chip 2.21k Ohm 0.1W 1% 0603")
      (fields (field (name "TOLERANCE") "±1%") (field (name "Comment") "Thick Film"))
      (libsource (lib "analogboard_v2") (part "RES_2K21_0603_1%"))
    )
    (comp (ref "R14")
      (value "2K21")
      (footprint "RESC1608N")
      (description "Resistor SMD chip 2.21k Ohm 0.1W 1% 0603")
      (fields (field (name "TOLERANCE") "±1%") (field (name "Comment") "Thick Film"))
      (libsource (lib "analogboard_v2") (part "RES_2K21_0603_1%"))
    )
    (comp (ref "R15")
      (value "2K21")
      (footprint "RESC1608N")
      (description "Resistor SMD chip 2.21k Ohm 0.1W 1% 0603")
      (fields (field (name "TOLERANCE") "±1%") (field (name "Comment") "Thick Film"))
      (libsource (lib "analogboard_v2") (part "RES_2K21_0603_1%"))
    )
    (comp (ref "R16")
      (value "2K21")
      (footprint "RESC1608N")
      (description "Resistor SMD chip 2.21k Ohm 0.1W 1% 0603")
      (fields (field (name "TOLERANCE") "±1%") (field (name "Comment") "Thick Film"))
      (libsource (lib "analogboard_v2") (part "RES_2K21_0603_1%"))
    )
    (comp (ref "R17")
      (value "RH73X2A50GNTN")
      (footprint "RES_RH732A_TYC")
      (description "No Description Available")
      (fields (field (name "COPYRIGHT") "Copyright (C) 2022 Ultra Librarian. All rights reserved."))
      (libsource (lib "RH73X2A50GNTN") (part "RH73X2A50GNTN"))
    )
    (comp (ref "R18")
      (value "CRCW08054M12FKEA")
      (footprint "RC0805N_VIS")
      (description "No Description Available")
      (fields (field (name "COPYRIGHT") "Copyright (C) 2022 Ultra Librarian. All rights reserved."))
      (libsource (lib "CRCW08054M12FKEA") (part "CRCW08054M12FKEA"))
    )
    (comp (ref "R19")
      (value "RC0603JR-07100RL")
      (footprint "RC0603N_YAG")
      (description "No Description Available")
      (fields (field (name "COPYRIGHT") "Copyright (C) 2022 Ultra Librarian. All rights reserved."))
      (libsource (lib "RC0603JR-07100RL") (part "RC0603JR-07100RL"))
    )
    (comp (ref "R20")
      (value "100K")
      (footprint "RESC1608N")
      (description "Resistor SMD chip 100k Ohm 0.1W 1% 0603")
      (fields (field (name "TOLERANCE") "±1%") (field (name "Comment") "Thick Film"))
      (libsource (lib "analogboard_v2") (part "RES_100K_0603_1%"))
    )
    (comp (ref "R21")
      (value "100K")
      (footprint "RESC1608N")
      (description "Resistor SMD chip 100k Ohm 0.1W 1% 0603")
      (fields (field (name "TOLERANCE") "±1%") (field (name "Comment") "Thick Film"))
      (libsource (lib "analogboard_v2") (part "RES_100K_0603_1%"))
    )
    (comp (ref "S1")
      (value "SWITCH_JS202011CQN_DPDT")
      (footprint "PCBComponent_1")
      (libsource (lib "dpdt_switch") (part "SWITCH_JS202011CQN_DPDT"))
    )
    (comp (ref "S2")
      (value "SWITCH_JS202011CQN_DPDT")
      (footprint "PCBComponent_1")
      (libsource (lib "dpdt_switch") (part "SWITCH_JS202011CQN_DPDT"))
    )
    (comp (ref "S3")
      (value "SWITCH_JS202011CQN_DPDT")
      (footprint "PCBComponent_1")
      (libsource (lib "analogboard_v2") (part "SWITCH_JS202011CQN_DPDT"))
    )
    (comp (ref "S4")
      (value "SWITCH_JS202011CQN_DPDT")
      (footprint "PCBComponent_1")
      (libsource (lib "analogboard_v2") (part "SWITCH_JS202011CQN_DPDT"))
    )
    (comp (ref "S5")
      (value "SWITCH_JS202011CQN_DPDT")
      (footprint "PCBComponent_1")
      (libsource (lib "dpdt_switch") (part "SWITCH_JS202011CQN_DPDT"))
    )
    (comp (ref "U1")
      (value "LP3961ES-2.5")
      (footprint "TS5B_TEX")
      (description "No Description Available")
      (fields (field (name "COPYRIGHT") "Copyright (C) 2022 Ultra Librarian. All rights reserved."))
      (libsource (lib "LP3961ES-2P5") (part "LP3961ES-2.5"))
    )
    (comp (ref "U2")
      (value "BD00C0AWHFP-CTR")
      (footprint "HRP5_BD00C0_ROM")
      (description "No Description Available")
      (fields (field (name "COPYRIGHT") "Copyright (C) 2022 Ultra Librarian. All rights reserved."))
      (libsource (lib "BD00C0AWHFP-CTR") (part "BD00C0AWHFP-CTR"))
    )
    (comp (ref "U3")
      (value "BD00C0AWHFP-CTR")
      (footprint "HRP5_BD00C0_ROM")
      (description "No Description Available")
      (fields (field (name "COPYRIGHT") "Copyright (C) 2022 Ultra Librarian. All rights reserved."))
      (libsource (lib "BD00C0AWHFP-CTR") (part "BD00C0AWHFP-CTR"))
    )
    (comp (ref "U4")
      (value "BD33C0AFP-CE2")
      (footprint "TO252-3_ROM")
      (description "No Description Available")
      (fields (field (name "COPYRIGHT") "Copyright (C) 2022 Ultra Librarian. All rights reserved."))
      (libsource (lib "BD33C0AFP-CE2") (part "BD33C0AFP-CE2"))
    )
    (comp (ref "U5")
      (value "BD00C0AWHFP-CTR")
      (footprint "HRP5_BD00C0_ROM")
      (description "No Description Available")
      (fields (field (name "COPYRIGHT") "Copyright (C) 2022 Ultra Librarian. All rights reserved."))
      (libsource (lib "BD00C0AWHFP-CTR") (part "BD00C0AWHFP-CTR"))
    )
    (comp (ref "U6")
      (value "BD00C0AWHFP-CTR")
      (footprint "HRP5_BD00C0_ROM")
      (description "No Description Available")
      (fields (field (name "COPYRIGHT") "Copyright (C) 2022 Ultra Librarian. All rights reserved."))
      (libsource (lib "BD00C0AWHFP-CTR") (part "BD00C0AWHFP-CTR"))
    )
    (comp (ref "U7")
      (value "REF5025AIDG4")
      (footprint "D8")
      (description "No Description Available")
      (fields (field (name "COPYRIGHT") "Copyright (C) 2021 Ultra Librarian. All rights reserved."))
      (libsource (lib "REF5025AIDG4") (part "REF5025AIDG4"))
    )
    (comp (ref "U8")
      (value "SN74LVCH16T245DGGR")
      (footprint "DGG48")
      (description "No Description Available")
      (fields (field (name "COPYRIGHT") "Copyright (C) 2022 Ultra Librarian. All rights reserved."))
      (libsource (lib "SN74LVCH16T245DGGR") (part "SN74LVCH16T245DGGR"))
    )
    (comp (ref "U9")
      (value "DAC7614EB")
      (footprint "DB20")
      (description "No Description Available")
      (fields (field (name "COPYRIGHT") "Copyright (C) 2022 Ultra Librarian. All rights reserved."))
      (libsource (lib "DAC7614EB") (part "DAC7614EB"))
    )
    (comp (ref "U10")
      (value "DAC7614EB")
      (footprint "DB20")
      (description "No Description Available")
      (fields (field (name "COPYRIGHT") "Copyright (C) 2022 Ultra Librarian. All rights reserved."))
      (libsource (lib "DAC7614EB") (part "DAC7614EB"))
    )
    (comp (ref "U11")
      (value "TLV2771CDBVR")
      (footprint "DBV5")
      (description "No Description Available")
      (fields (field (name "COPYRIGHT") "Copyright (C) 2022 Ultra Librarian. All rights reserved."))
      (libsource (lib "TLV2771CDBVR") (part "TLV2771CDBVR"))
    )
    (comp (ref "U12")
      (value "BC817W")
      (footprint "SOT323_NEX")
      (description "No Description Available")
      (fields (field (name "COPYRIGHT") "Copyright (C) 2022 Ultra Librarian. All rights reserved."))
      (libsource (lib "BC817W") (part "BC817W"))
    )
    (comp (ref "U13")
      (value "TLV2771CDBVR")
      (footprint "DBV5")
      (description "No Description Available")
      (fields (field (name "COPYRIGHT") "Copyright (C) 2022 Ultra Librarian. All rights reserved."))
      (libsource (lib "TLV2771CDBVR") (part "TLV2771CDBVR"))
    )
    (comp (ref "U14")
      (value "BC817W")
      (footprint "SOT323_NEX")
      (description "No Description Available")
      (fields (field (name "COPYRIGHT") "Copyright (C) 2022 Ultra Librarian. All rights reserved."))
      (libsource (lib "BC817W") (part "BC817W"))
    )
    (comp (ref "U15")
      (value "TLV2771CDBVR")
      (footprint "DBV5")
      (description "No Description Available")
      (fields (field (name "COPYRIGHT") "Copyright (C) 2022 Ultra Librarian. All rights reserved."))
      (libsource (lib "TLV2771CDBVR") (part "TLV2771CDBVR"))
    )
    (comp (ref "U16")
      (value "BC817W")
      (footprint "SOT323_NEX")
      (description "No Description Available")
      (fields (field (name "COPYRIGHT") "Copyright (C) 2022 Ultra Librarian. All rights reserved."))
      (libsource (lib "BC817W") (part "BC817W"))
    )
    (comp (ref "U17")
      (value "DAC7614EB")
      (footprint "DB20")
      (description "No Description Available")
      (fields (field (name "COPYRIGHT") "Copyright (C) 2022 Ultra Librarian. All rights reserved."))
      (libsource (lib "DAC7614EB") (part "DAC7614EB"))
    )
    (comp (ref "U18")
      (value "TLV2771CDBVR")
      (footprint "DBV5")
      (description "No Description Available")
      (fields (field (name "COPYRIGHT") "Copyright (C) 2022 Ultra Librarian. All rights reserved."))
      (libsource (lib "TLV2771CDBVR") (part "TLV2771CDBVR"))
    )
    (comp (ref "U19")
      (value "BC817W")
      (footprint "SOT323_NEX")
      (description "No Description Available")
      (fields (field (name "COPYRIGHT") "Copyright (C) 2022 Ultra Librarian. All rights reserved."))
      (libsource (lib "BC817W") (part "BC817W"))
    )
    (comp (ref "U20")
      (value "TLV2771CDBVR")
      (footprint "DBV5")
      (description "No Description Available")
      (fields (field (name "COPYRIGHT") "Copyright (C) 2022 Ultra Librarian. All rights reserved."))
      (libsource (lib "TLV2771CDBVR") (part "TLV2771CDBVR"))
    )
    (comp (ref "U21")
      (value "BC817W")
      (footprint "SOT323_NEX")
      (description "No Description Available")
      (fields (field (name "COPYRIGHT") "Copyright (C) 2022 Ultra Librarian. All rights reserved."))
      (libsource (lib "BC817W") (part "BC817W"))
    )
    (comp (ref "U22")
      (value "SN74LVCH16T245DGGR")
      (footprint "DGG48")
      (description "No Description Available")
      (fields (field (name "COPYRIGHT") "Copyright (C) 2022 Ultra Librarian. All rights reserved."))
      (libsource (lib "SN74LVCH16T245DGGR") (part "SN74LVCH16T245DGGR"))
    )
    (comp (ref "U23")
      (value "TLV2771CDBVR")
      (footprint "DBV5")
      (description "No Description Available")
      (fields (field (name "COPYRIGHT") "Copyright (C) 2022 Ultra Librarian. All rights reserved."))
      (libsource (lib "TLV2771CDBVR") (part "TLV2771CDBVR"))
    )
    (comp (ref "U24")
      (value "BC817W")
      (footprint "SOT323_NEX")
      (description "No Description Available")
      (fields (field (name "COPYRIGHT") "Copyright (C) 2022 Ultra Librarian. All rights reserved."))
      (libsource (lib "BC817W") (part "BC817W"))
    )
    (comp (ref "U25")
      (value "ADS8344E")
      (footprint "DBQ20")
      (description "No Description Available")
      (fields (field (name "COPYRIGHT") "Copyright (C) 2022 Ultra Librarian. All rights reserved."))
      (libsource (lib "ADS8344E") (part "ADS8344E"))
    )
    (comp (ref "U26")
      (value "TLV2771CDBVR")
      (footprint "DBV5")
      (description "No Description Available")
      (fields (field (name "COPYRIGHT") "Copyright (C) 2022 Ultra Librarian. All rights reserved."))
      (libsource (lib "TLV2771CDBVR") (part "TLV2771CDBVR"))
    )
    (comp (ref "U27")
      (value "OPA380AIDGKT")
      (footprint "DGK8")
      (description "No Description Available")
      (fields (field (name "COPYRIGHT") "Copyright (C) 2022 Ultra Librarian. All rights reserved."))
      (libsource (lib "OPA380AIDGKT") (part "OPA380AIDGKT"))
    )
    (comp (ref "VDD_1")
      (value "Red")
      (footprint "LED-0603-RED")
      (description "LED 0603 SMD Hyper Red 630nm 220mcd 20mA")
      (libsource (lib "PBL - Light Sources") (part "LED_SMD_Red_0603_220mcd"))
    )
  )
  (nets
    (net (code "1") (name "/ACK") (class "Default")
      (node (ref "J22") (pin "9") (pinfunction "9_9") (pintype "passive"))
      (node (ref "U8") (pin "27") (pinfunction "2A7_27") (pintype "bidirectional"))
    )
    (net (code "2") (name "/ACKX_PULSE_EXT<0>") (class "Default")
      (node (ref "J18") (pin "3") (pinfunction "3_3") (pintype "passive"))
      (node (ref "U8") (pin "47") (pinfunction "1A1_47") (pintype "bidirectional"))
    )
    (net (code "3") (name "/ACKX_PULSE_EXT<1>") (class "Default")
      (node (ref "J18") (pin "6") (pinfunction "6_6") (pintype "passive"))
      (node (ref "U8") (pin "46") (pinfunction "1A2_46") (pintype "bidirectional"))
    )
    (net (code "4") (name "/ACKX_PULSE_EXT<2>") (class "Default")
      (node (ref "J18") (pin "9") (pinfunction "9_9") (pintype "passive"))
      (node (ref "U8") (pin "44") (pinfunction "1A3_44") (pintype "bidirectional"))
    )
    (net (code "5") (name "/ACKX_PULSE_EXT<3>") (class "Default")
      (node (ref "J18") (pin "12") (pinfunction "12_12") (pintype "passive"))
      (node (ref "U8") (pin "43") (pinfunction "1A4_43") (pintype "bidirectional"))
    )
    (net (code "6") (name "/ACKX_PULSE_EXT<4>") (class "Default")
      (node (ref "J18") (pin "15") (pinfunction "15_15") (pintype "passive"))
      (node (ref "U8") (pin "41") (pinfunction "1A5_41") (pintype "bidirectional"))
    )
    (net (code "7") (name "/ACKX_PULSE_EXT<5>") (class "Default")
      (node (ref "J18") (pin "18") (pinfunction "18_18") (pintype "passive"))
      (node (ref "U8") (pin "40") (pinfunction "1A6_40") (pintype "bidirectional"))
    )
    (net (code "8") (name "/ACKX_PULSE_EXT<6>") (class "Default")
      (node (ref "J18") (pin "21") (pinfunction "21_21") (pintype "passive"))
      (node (ref "U8") (pin "38") (pinfunction "1A7_38") (pintype "bidirectional"))
    )
    (net (code "9") (name "/ACKX_PULSE_EXT<7>") (class "Default")
      (node (ref "J18") (pin "24") (pinfunction "24_24") (pintype "passive"))
      (node (ref "U8") (pin "37") (pinfunction "1A8_37") (pintype "bidirectional"))
    )
    (net (code "10") (name "/ACKX_PULSE_EXT<8>") (class "Default")
      (node (ref "J18") (pin "27") (pinfunction "27_27") (pintype "passive"))
      (node (ref "U8") (pin "36") (pinfunction "2A1_36") (pintype "bidirectional"))
    )
    (net (code "11") (name "/ACKX_PULSE_EXT<9>") (class "Default")
      (node (ref "J18") (pin "30") (pinfunction "30_30") (pintype "passive"))
      (node (ref "U8") (pin "35") (pinfunction "2A2_35") (pintype "bidirectional"))
    )
    (net (code "12") (name "/ACKX_PULSE_EXT_33<0>") (class "Default")
      (node (ref "J11") (pin "10") (pinfunction "10_10") (pintype "passive"))
      (node (ref "U8") (pin "2") (pinfunction "1B1_2") (pintype "bidirectional"))
    )
    (net (code "13") (name "/ACKX_PULSE_EXT_33<1>") (class "Default")
      (node (ref "J11") (pin "5") (pinfunction "5_5") (pintype "passive"))
      (node (ref "U8") (pin "3") (pinfunction "1B2_3") (pintype "bidirectional"))
    )
    (net (code "14") (name "/ACKX_PULSE_EXT_33<2>") (class "Default")
      (node (ref "J11") (pin "9") (pinfunction "9_9") (pintype "passive"))
      (node (ref "U8") (pin "5") (pinfunction "1B3_5") (pintype "bidirectional"))
    )
    (net (code "15") (name "/ACKX_PULSE_EXT_33<3>") (class "Default")
      (node (ref "J11") (pin "4") (pinfunction "4_4") (pintype "passive"))
      (node (ref "U8") (pin "6") (pinfunction "1B4_6") (pintype "bidirectional"))
    )
    (net (code "16") (name "/ACKX_PULSE_EXT_33<4>") (class "Default")
      (node (ref "J11") (pin "8") (pinfunction "8_8") (pintype "passive"))
      (node (ref "U8") (pin "8") (pinfunction "1B5_8") (pintype "bidirectional"))
    )
    (net (code "17") (name "/ACKX_PULSE_EXT_33<5>") (class "Default")
      (node (ref "J11") (pin "3") (pinfunction "3_3") (pintype "passive"))
      (node (ref "U8") (pin "9") (pinfunction "1B6_9") (pintype "bidirectional"))
    )
    (net (code "18") (name "/ACKX_PULSE_EXT_33<6>") (class "Default")
      (node (ref "J11") (pin "7") (pinfunction "7_7") (pintype "passive"))
      (node (ref "U8") (pin "11") (pinfunction "1B7_11") (pintype "bidirectional"))
    )
    (net (code "19") (name "/ACKX_PULSE_EXT_33<7>") (class "Default")
      (node (ref "J11") (pin "2") (pinfunction "2_2") (pintype "passive"))
      (node (ref "U8") (pin "12") (pinfunction "1B8_12") (pintype "bidirectional"))
    )
    (net (code "20") (name "/ACKX_PULSE_EXT_33<8>") (class "Default")
      (node (ref "J11") (pin "6") (pinfunction "6_6") (pintype "passive"))
      (node (ref "U8") (pin "13") (pinfunction "2B1_13") (pintype "bidirectional"))
    )
    (net (code "21") (name "/ACKX_PULSE_EXT_33<9>") (class "Default")
      (node (ref "J11") (pin "1") (pinfunction "1_1") (pintype "passive"))
      (node (ref "U8") (pin "14") (pinfunction "2B2_14") (pintype "bidirectional"))
    )
    (net (code "22") (name "/ACK_33") (class "Default")
      (node (ref "J27") (pin "7") (pinfunction "7_7") (pintype "passive"))
      (node (ref "U8") (pin "22") (pinfunction "2B7_22") (pintype "bidirectional"))
    )
    (net (code "23") (name "/ADDRX<0>") (class "Default")
      (node (ref "J22") (pin "8") (pinfunction "8_8") (pintype "passive"))
      (node (ref "J27") (pin "4") (pinfunction "4_4") (pintype "passive"))
    )
    (net (code "24") (name "/ADDRX<1>") (class "Default")
      (node (ref "J22") (pin "5") (pinfunction "5_5") (pintype "passive"))
      (node (ref "J27") (pin "3") (pinfunction "3_3") (pintype "passive"))
    )
    (net (code "25") (name "/ADDRX<2>") (class "Default")
      (node (ref "J22") (pin "6") (pinfunction "6_6") (pintype "passive"))
      (node (ref "J27") (pin "2") (pinfunction "2_2") (pintype "passive"))
    )
    (net (code "26") (name "/ADDRX<3>") (class "Default")
      (node (ref "J22") (pin "3") (pinfunction "3_3") (pintype "passive"))
      (node (ref "J27") (pin "1") (pinfunction "1_1") (pintype "passive"))
    )
    (net (code "27") (name "/ADDRY<0>") (class "Default")
      (node (ref "J22") (pin "16") (pinfunction "16_16") (pintype "passive"))
      (node (ref "J27") (pin "12") (pinfunction "12_12") (pintype "passive"))
    )
    (net (code "28") (name "/ADDRY<1>") (class "Default")
      (node (ref "J22") (pin "13") (pinfunction "13_13") (pintype "passive"))
      (node (ref "J27") (pin "11") (pinfunction "11_11") (pintype "passive"))
    )
    (net (code "29") (name "/ADDRY<2>") (class "Default")
      (node (ref "J22") (pin "14") (pinfunction "14_14") (pintype "passive"))
      (node (ref "J27") (pin "10") (pinfunction "10_10") (pintype "passive"))
    )
    (net (code "30") (name "/ADDRY<3>") (class "Default")
      (node (ref "J22") (pin "11") (pinfunction "11_11") (pintype "passive"))
      (node (ref "J27") (pin "9") (pinfunction "9_9") (pintype "passive"))
    )
    (net (code "31") (name "/AER_DIS_EXT") (class "Default")
      (node (ref "J24") (pin "8") (pinfunction "8_8") (pintype "passive"))
      (node (ref "S4") (pin "5") (pinfunction "5_5") (pintype "passive"))
    )
    (net (code "32") (name "/AER_RST") (class "Default")
      (node (ref "J22") (pin "12") (pinfunction "12_12") (pintype "passive"))
      (node (ref "S5") (pin "6") (pinfunction "6_6") (pintype "passive"))
      (node (ref "U8") (pin "29") (pinfunction "2A6_29") (pintype "bidirectional"))
    )
    (net (code "33") (name "/AER_RST_33") (class "Default")
      (node (ref "J27") (pin "8") (pinfunction "8_8") (pintype "passive"))
      (node (ref "U8") (pin "20") (pinfunction "2B6_20") (pintype "bidirectional"))
    )
    (net (code "34") (name "/BUSY") (class "Default")
      (node (ref "J31") (pin "10") (pinfunction "10_10") (pintype "passive"))
      (node (ref "U25") (pin "16") (pinfunction "BUSY_16") (pintype "output"))
    )
    (net (code "35") (name "/CLK") (class "Default")
      (node (ref "J31") (pin "2") (pinfunction "2_2") (pintype "passive"))
      (node (ref "U10") (pin "13") (pinfunction "CLK_13") (pintype "passive"))
      (node (ref "U17") (pin "13") (pinfunction "CLK_13") (pintype "passive"))
      (node (ref "U25") (pin "19") (pinfunction "DCLK_19") (pintype "input"))
      (node (ref "U9") (pin "13") (pinfunction "CLK_13") (pintype "passive"))
    )
    (net (code "36") (name "/CSb_ADC") (class "Default")
      (node (ref "J31") (pin "5") (pinfunction "5_5") (pintype "passive"))
      (node (ref "U25") (pin "18") (pinfunction "*CS_18") (pintype "input"))
    )
    (net (code "37") (name "/CSb_IDAC") (class "Default")
      (node (ref "J31") (pin "4") (pinfunction "4_4") (pintype "passive"))
      (node (ref "U17") (pin "14") (pinfunction "*CS_14") (pintype "input"))
    )
    (net (code "38") (name "/CSb_IDAC_scaled") (class "Default")
      (node (ref "J31") (pin "8") (pinfunction "8_8") (pintype "passive"))
      (node (ref "U10") (pin "14") (pinfunction "*CS_14") (pintype "input"))
    )
    (net (code "39") (name "/CSb_VDAC") (class "Default")
      (node (ref "J31") (pin "7") (pinfunction "7_7") (pintype "passive"))
      (node (ref "U9") (pin "14") (pinfunction "*CS_14") (pintype "input"))
    )
    (net (code "40") (name "/HEM_OUT") (class "Default")
      (node (ref "C70") (pin "1") (pinfunction "1_1") (pintype "passive"))
      (node (ref "J21") (pin "14") (pinfunction "14_14") (pintype "passive"))
      (node (ref "R18") (pin "2") (pinfunction "2_2") (pintype "passive"))
      (node (ref "U27") (pin "2") (pinfunction "IN-_2") (pintype "input"))
    )
    (net (code "41") (name "/HEM_OUT_I2V") (class "Default")
      (node (ref "C70") (pin "2") (pinfunction "2_2") (pintype "passive"))
      (node (ref "J12") (pin "1") (pinfunction "1_1") (pintype "passive"))
      (node (ref "J14") (pin "1") (pinfunction "1_1") (pintype "passive"))
      (node (ref "R18") (pin "1") (pinfunction "1_1") (pintype "passive"))
      (node (ref "U25") (pin "2") (pinfunction "CH1_2") (pintype "input"))
      (node (ref "U27") (pin "6") (pinfunction "OUT_6") (pintype "output"))
    )
    (net (code "42") (name "/IBLEED") (class "Default")
      (node (ref "J17") (pin "1") (pinfunction "1_1") (pintype "passive"))
      (node (ref "J21") (pin "6") (pinfunction "6_6") (pintype "passive"))
      (node (ref "U12") (pin "3") (pinfunction "COLLECTOR_3") (pintype "passive"))
    )
    (net (code "43") (name "/ISLEW") (class "Default")
      (node (ref "J21") (pin "4") (pinfunction "4_4") (pintype "passive"))
      (node (ref "J28") (pin "1") (pinfunction "1_1") (pintype "passive"))
      (node (ref "U19") (pin "3") (pinfunction "COLLECTOR_3") (pintype "passive"))
    )
    (net (code "44") (name "/ISPK") (class "Default")
      (node (ref "J21") (pin "5") (pinfunction "5_5") (pintype "passive"))
      (node (ref "J30") (pin "1") (pinfunction "1_1") (pintype "passive"))
      (node (ref "U21") (pin "3") (pinfunction "COLLECTOR_3") (pintype "passive"))
    )
    (net (code "45") (name "/ISPKFAST") (class "Default")
      (node (ref "J21") (pin "9") (pinfunction "9_9") (pintype "passive"))
      (node (ref "J32") (pin "1") (pinfunction "1_1") (pintype "passive"))
      (node (ref "U24") (pin "3") (pinfunction "COLLECTOR_3") (pintype "passive"))
    )
    (net (code "46") (name "/ITAIL") (class "Default")
      (node (ref "J21") (pin "8") (pinfunction "8_8") (pintype "passive"))
      (node (ref "J23") (pin "1") (pinfunction "1_1") (pintype "passive"))
      (node (ref "U16") (pin "3") (pinfunction "COLLECTOR_3") (pintype "passive"))
    )
    (net (code "47") (name "/ITH") (class "Default")
      (node (ref "J19") (pin "1") (pinfunction "1_1") (pintype "passive"))
      (node (ref "J21") (pin "7") (pinfunction "7_7") (pintype "passive"))
      (node (ref "U14") (pin "3") (pinfunction "COLLECTOR_3") (pintype "passive"))
    )
    (net (code "48") (name "/LDACb") (class "Default")
      (node (ref "J31") (pin "1") (pinfunction "1_1") (pintype "passive"))
      (node (ref "U10") (pin "18") (pinfunction "*LOADDACS_18") (pintype "passive"))
      (node (ref "U17") (pin "18") (pinfunction "*LOADDACS_18") (pintype "passive"))
      (node (ref "U9") (pin "18") (pinfunction "*LOADDACS_18") (pintype "passive"))
    )
    (net (code "49") (name "/N_COX_OFF_EXT<0>") (class "Default")
      (node (ref "J18") (pin "2") (pinfunction "2_2") (pintype "passive"))
      (node (ref "J9") (pin "1") (pinfunction "1_1") (pintype "passive"))
    )
    (net (code "50") (name "/N_COX_OFF_EXT<1>") (class "Default")
      (node (ref "J18") (pin "5") (pinfunction "5_5") (pintype "passive"))
      (node (ref "J9") (pin "2") (pinfunction "2_2") (pintype "passive"))
    )
    (net (code "51") (name "/N_COX_OFF_EXT<2>") (class "Default")
      (node (ref "J18") (pin "8") (pinfunction "8_8") (pintype "passive"))
      (node (ref "J9") (pin "3") (pinfunction "3_3") (pintype "passive"))
    )
    (net (code "52") (name "/N_COX_OFF_EXT<3>") (class "Default")
      (node (ref "J18") (pin "11") (pinfunction "11_11") (pintype "passive"))
      (node (ref "J9") (pin "4") (pinfunction "4_4") (pintype "passive"))
    )
    (net (code "53") (name "/N_COX_OFF_EXT<4>") (class "Default")
      (node (ref "J18") (pin "14") (pinfunction "14_14") (pintype "passive"))
      (node (ref "J9") (pin "5") (pinfunction "5_5") (pintype "passive"))
    )
    (net (code "54") (name "/N_COX_OFF_EXT<5>") (class "Default")
      (node (ref "J10") (pin "1") (pinfunction "1_1") (pintype "passive"))
      (node (ref "J18") (pin "17") (pinfunction "17_17") (pintype "passive"))
    )
    (net (code "55") (name "/N_COX_OFF_EXT<6>") (class "Default")
      (node (ref "J10") (pin "2") (pinfunction "2_2") (pintype "passive"))
      (node (ref "J18") (pin "20") (pinfunction "20_20") (pintype "passive"))
    )
    (net (code "56") (name "/N_COX_OFF_EXT<7>") (class "Default")
      (node (ref "J10") (pin "3") (pinfunction "3_3") (pintype "passive"))
      (node (ref "J18") (pin "23") (pinfunction "23_23") (pintype "passive"))
    )
    (net (code "57") (name "/N_COX_OFF_EXT<8>") (class "Default")
      (node (ref "J10") (pin "4") (pinfunction "4_4") (pintype "passive"))
      (node (ref "J18") (pin "26") (pinfunction "26_26") (pintype "passive"))
    )
    (net (code "58") (name "/N_COX_OFF_EXT<9>") (class "Default")
      (node (ref "J10") (pin "5") (pinfunction "5_5") (pintype "passive"))
      (node (ref "J18") (pin "29") (pinfunction "29_29") (pintype "passive"))
    )
    (net (code "59") (name "/N_COX_ON_EXT<0>") (class "Default")
      (node (ref "J18") (pin "1") (pinfunction "1_1") (pintype "passive"))
      (node (ref "J9") (pin "6") (pinfunction "6_6") (pintype "passive"))
    )
    (net (code "60") (name "/N_COX_ON_EXT<1>") (class "Default")
      (node (ref "J18") (pin "4") (pinfunction "4_4") (pintype "passive"))
      (node (ref "J9") (pin "7") (pinfunction "7_7") (pintype "passive"))
    )
    (net (code "61") (name "/N_COX_ON_EXT<2>") (class "Default")
      (node (ref "J18") (pin "7") (pinfunction "7_7") (pintype "passive"))
      (node (ref "J9") (pin "8") (pinfunction "8_8") (pintype "passive"))
    )
    (net (code "62") (name "/N_COX_ON_EXT<3>") (class "Default")
      (node (ref "J18") (pin "10") (pinfunction "10_10") (pintype "passive"))
      (node (ref "J9") (pin "9") (pinfunction "9_9") (pintype "passive"))
    )
    (net (code "63") (name "/N_COX_ON_EXT<4>") (class "Default")
      (node (ref "J18") (pin "13") (pinfunction "13_13") (pintype "passive"))
      (node (ref "J9") (pin "10") (pinfunction "10_10") (pintype "passive"))
    )
    (net (code "64") (name "/N_COX_ON_EXT<5>") (class "Default")
      (node (ref "J10") (pin "6") (pinfunction "6_6") (pintype "passive"))
      (node (ref "J18") (pin "16") (pinfunction "16_16") (pintype "passive"))
    )
    (net (code "65") (name "/N_COX_ON_EXT<6>") (class "Default")
      (node (ref "J10") (pin "7") (pinfunction "7_7") (pintype "passive"))
      (node (ref "J18") (pin "19") (pinfunction "19_19") (pintype "passive"))
    )
    (net (code "66") (name "/N_COX_ON_EXT<7>") (class "Default")
      (node (ref "J10") (pin "8") (pinfunction "8_8") (pintype "passive"))
      (node (ref "J18") (pin "22") (pinfunction "22_22") (pintype "passive"))
    )
    (net (code "67") (name "/N_COX_ON_EXT<8>") (class "Default")
      (node (ref "J10") (pin "9") (pinfunction "9_9") (pintype "passive"))
      (node (ref "J18") (pin "25") (pinfunction "25_25") (pintype "passive"))
    )
    (net (code "68") (name "/N_COX_ON_EXT<9>") (class "Default")
      (node (ref "J10") (pin "10") (pinfunction "10_10") (pintype "passive"))
      (node (ref "J18") (pin "28") (pinfunction "28_28") (pintype "passive"))
    )
    (net (code "69") (name "/N_P_EXT<0>") (class "Default")
      (node (ref "J24") (pin "9") (pinfunction "9_9") (pintype "passive"))
      (node (ref "J29") (pin "2") (pinfunction "2_2") (pintype "passive"))
    )
    (net (code "70") (name "/N_P_EXT<1>") (class "Default")
      (node (ref "J24") (pin "11") (pinfunction "11_11") (pintype "passive"))
      (node (ref "J29") (pin "4") (pinfunction "4_4") (pintype "passive"))
    )
    (net (code "71") (name "/N_P_EXT<2>") (class "Default")
      (node (ref "J24") (pin "13") (pinfunction "13_13") (pintype "passive"))
      (node (ref "J29") (pin "6") (pinfunction "6_6") (pintype "passive"))
    )
    (net (code "72") (name "/N_P_EXT<3>") (class "Default")
      (node (ref "J24") (pin "15") (pinfunction "15_15") (pintype "passive"))
      (node (ref "J29") (pin "8") (pinfunction "8_8") (pintype "passive"))
    )
    (net (code "73") (name "/N_P_EXT<4>") (class "Default")
      (node (ref "J24") (pin "17") (pinfunction "17_17") (pintype "passive"))
      (node (ref "J29") (pin "10") (pinfunction "10_10") (pintype "passive"))
    )
    (net (code "74") (name "/N_P_EXT<5>") (class "Default")
      (node (ref "J24") (pin "19") (pinfunction "19_19") (pintype "passive"))
      (node (ref "J29") (pin "12") (pinfunction "12_12") (pintype "passive"))
    )
    (net (code "75") (name "/N_P_EXT<6>") (class "Default")
      (node (ref "J24") (pin "21") (pinfunction "21_21") (pintype "passive"))
      (node (ref "J29") (pin "14") (pinfunction "14_14") (pintype "passive"))
    )
    (net (code "76") (name "/N_P_EXT<7>") (class "Default")
      (node (ref "J24") (pin "23") (pinfunction "23_23") (pintype "passive"))
      (node (ref "J29") (pin "16") (pinfunction "16_16") (pintype "passive"))
    )
    (net (code "77") (name "/N_P_EXT<8>") (class "Default")
      (node (ref "J24") (pin "25") (pinfunction "25_25") (pintype "passive"))
      (node (ref "J29") (pin "18") (pinfunction "18_18") (pintype "passive"))
    )
    (net (code "78") (name "/N_P_EXT<9>") (class "Default")
      (node (ref "J24") (pin "27") (pinfunction "27_27") (pintype "passive"))
      (node (ref "J29") (pin "20") (pinfunction "20_20") (pintype "passive"))
    )
    (net (code "79") (name "/N_P_EXT<10>") (class "Default")
      (node (ref "J24") (pin "29") (pinfunction "29_29") (pintype "passive"))
      (node (ref "J29") (pin "22") (pinfunction "22_22") (pintype "passive"))
    )
    (net (code "80") (name "/POLING_MODE_SW") (class "Default")
      (node (ref "J24") (pin "3") (pinfunction "3_3") (pintype "passive"))
      (node (ref "S5") (pin "5") (pinfunction "5_5") (pintype "passive"))
    )
    (net (code "81") (name "/POS_CALIB") (class "Default")
      (node (ref "J24") (pin "4") (pinfunction "4_4") (pintype "passive"))
      (node (ref "J26") (pin "4") (pinfunction "4_4") (pintype "passive"))
    )
    (net (code "82") (name "/POS_TEST") (class "Default")
      (node (ref "J24") (pin "5") (pinfunction "5_5") (pintype "passive"))
      (node (ref "R19") (pin "1") (pinfunction "1_1") (pintype "passive"))
    )
    (net (code "83") (name "/POS_TEST_CAMP") (class "Default")
      (node (ref "C71") (pin "1") (pinfunction "1_1") (pintype "passive"))
      (node (ref "J13") (pin "1") (pinfunction "1_1") (pintype "passive"))
      (node (ref "J14") (pin "2") (pinfunction "2_2") (pintype "passive"))
      (node (ref "R17") (pin "2") (pinfunction "2_2") (pintype "passive"))
      (node (ref "U25") (pin "1") (pinfunction "CH0_1") (pintype "input"))
      (node (ref "U26") (pin "1") (pinfunction "OUT_1") (pintype "output"))
    )
    (net (code "84") (name "/REQOFF") (class "Default")
      (node (ref "J22") (pin "10") (pinfunction "10_10") (pintype "passive"))
      (node (ref "J27") (pin "6") (pinfunction "6_6") (pintype "passive"))
    )
    (net (code "85") (name "/REQON") (class "Default")
      (node (ref "J22") (pin "7") (pinfunction "7_7") (pintype "passive"))
      (node (ref "J27") (pin "5") (pinfunction "5_5") (pintype "passive"))
    )
    (net (code "86") (name "/RESETb") (class "Default")
      (node (ref "J31") (pin "6") (pinfunction "6_6") (pintype "passive"))
      (node (ref "U10") (pin "19") (pinfunction "*RESET_19") (pintype "input"))
      (node (ref "U17") (pin "19") (pinfunction "*RESET_19") (pintype "input"))
      (node (ref "U9") (pin "19") (pinfunction "*RESET_19") (pintype "input"))
    )
    (net (code "87") (name "/SCLK") (class "Default")
      (node (ref "J21") (pin "22") (pinfunction "22_22") (pintype "passive"))
      (node (ref "U8") (pin "32") (pinfunction "2A4_32") (pintype "bidirectional"))
    )
    (net (code "88") (name "/SCLK_33") (class "Default")
      (node (ref "J20") (pin "2") (pinfunction "2_2") (pintype "passive"))
      (node (ref "U8") (pin "17") (pinfunction "2B4_17") (pintype "bidirectional"))
    )
    (net (code "89") (name "/SDI") (class "Default")
      (node (ref "J31") (pin "3") (pinfunction "3_3") (pintype "passive"))
      (node (ref "U10") (pin "12") (pinfunction "SDI_12") (pintype "input"))
      (node (ref "U17") (pin "12") (pinfunction "SDI_12") (pintype "input"))
      (node (ref "U25") (pin "17") (pinfunction "DIN_17") (pintype "input"))
      (node (ref "U9") (pin "12") (pinfunction "SDI_12") (pintype "input"))
    )
    (net (code "90") (name "/SDOUT") (class "Default")
      (node (ref "J31") (pin "9") (pinfunction "9_9") (pintype "passive"))
      (node (ref "U25") (pin "15") (pinfunction "DOUT_15") (pintype "output"))
    )
    (net (code "91") (name "/SHIFT") (class "Default")
      (node (ref "J21") (pin "20") (pinfunction "20_20") (pintype "passive"))
      (node (ref "U8") (pin "33") (pinfunction "2A3_33") (pintype "bidirectional"))
    )
    (net (code "92") (name "/SHIFT_33") (class "Default")
      (node (ref "J20") (pin "1") (pinfunction "1_1") (pintype "passive"))
      (node (ref "U8") (pin "16") (pinfunction "2B3_16") (pintype "bidirectional"))
    )
    (net (code "93") (name "/SIN") (class "Default")
      (node (ref "J22") (pin "21") (pinfunction "21_21") (pintype "passive"))
      (node (ref "U8") (pin "30") (pinfunction "2A5_30") (pintype "bidirectional"))
    )
    (net (code "94") (name "/SIN_33") (class "Default")
      (node (ref "J20") (pin "4") (pinfunction "4_4") (pintype "passive"))
      (node (ref "U8") (pin "19") (pinfunction "2B5_19") (pintype "bidirectional"))
    )
    (net (code "95") (name "/SOUT") (class "Default")
      (node (ref "J20") (pin "3") (pinfunction "3_3") (pintype "passive"))
      (node (ref "J24") (pin "1") (pinfunction "1_1") (pintype "passive"))
    )
    (net (code "96") (name "/S_EXT<0>") (class "Default")
      (node (ref "J24") (pin "10") (pinfunction "10_10") (pintype "passive"))
      (node (ref "U22") (pin "47") (pinfunction "1A1_47") (pintype "bidirectional"))
    )
    (net (code "97") (name "/S_EXT<1>") (class "Default")
      (node (ref "J24") (pin "12") (pinfunction "12_12") (pintype "passive"))
      (node (ref "U22") (pin "46") (pinfunction "1A2_46") (pintype "bidirectional"))
    )
    (net (code "98") (name "/S_EXT<2>") (class "Default")
      (node (ref "J24") (pin "14") (pinfunction "14_14") (pintype "passive"))
      (node (ref "U22") (pin "44") (pinfunction "1A3_44") (pintype "bidirectional"))
    )
    (net (code "99") (name "/S_EXT<3>") (class "Default")
      (node (ref "J24") (pin "16") (pinfunction "16_16") (pintype "passive"))
      (node (ref "U22") (pin "43") (pinfunction "1A4_43") (pintype "bidirectional"))
    )
    (net (code "100") (name "/S_EXT<4>") (class "Default")
      (node (ref "J24") (pin "18") (pinfunction "18_18") (pintype "passive"))
      (node (ref "U22") (pin "41") (pinfunction "1A5_41") (pintype "bidirectional"))
    )
    (net (code "101") (name "/S_EXT<5>") (class "Default")
      (node (ref "J24") (pin "20") (pinfunction "20_20") (pintype "passive"))
      (node (ref "U22") (pin "40") (pinfunction "1A6_40") (pintype "bidirectional"))
    )
    (net (code "102") (name "/S_EXT<6>") (class "Default")
      (node (ref "J24") (pin "22") (pinfunction "22_22") (pintype "passive"))
      (node (ref "U22") (pin "38") (pinfunction "1A7_38") (pintype "bidirectional"))
    )
    (net (code "103") (name "/S_EXT<7>") (class "Default")
      (node (ref "J24") (pin "24") (pinfunction "24_24") (pintype "passive"))
      (node (ref "U22") (pin "37") (pinfunction "1A8_37") (pintype "bidirectional"))
    )
    (net (code "104") (name "/S_EXT<8>") (class "Default")
      (node (ref "J24") (pin "26") (pinfunction "26_26") (pintype "passive"))
      (node (ref "U22") (pin "36") (pinfunction "2A1_36") (pintype "bidirectional"))
    )
    (net (code "105") (name "/S_EXT<9>") (class "Default")
      (node (ref "J24") (pin "28") (pinfunction "28_28") (pintype "passive"))
      (node (ref "U22") (pin "35") (pinfunction "2A2_35") (pintype "bidirectional"))
    )
    (net (code "106") (name "/S_EXT<10>") (class "Default")
      (node (ref "J24") (pin "30") (pinfunction "30_30") (pintype "passive"))
      (node (ref "U22") (pin "33") (pinfunction "2A3_33") (pintype "bidirectional"))
    )
    (net (code "107") (name "/S_EXT_33<0>") (class "Default")
      (node (ref "J29") (pin "21") (pinfunction "21_21") (pintype "passive"))
      (node (ref "U22") (pin "2") (pinfunction "1B1_2") (pintype "bidirectional"))
    )
    (net (code "108") (name "/S_EXT_33<1>") (class "Default")
      (node (ref "J29") (pin "19") (pinfunction "19_19") (pintype "passive"))
      (node (ref "U22") (pin "3") (pinfunction "1B2_3") (pintype "bidirectional"))
    )
    (net (code "109") (name "/S_EXT_33<2>") (class "Default")
      (node (ref "J29") (pin "17") (pinfunction "17_17") (pintype "passive"))
      (node (ref "U22") (pin "5") (pinfunction "1B3_5") (pintype "bidirectional"))
    )
    (net (code "110") (name "/S_EXT_33<3>") (class "Default")
      (node (ref "J29") (pin "15") (pinfunction "15_15") (pintype "passive"))
      (node (ref "U22") (pin "6") (pinfunction "1B4_6") (pintype "bidirectional"))
    )
    (net (code "111") (name "/S_EXT_33<4>") (class "Default")
      (node (ref "J29") (pin "13") (pinfunction "13_13") (pintype "passive"))
      (node (ref "U22") (pin "8") (pinfunction "1B5_8") (pintype "bidirectional"))
    )
    (net (code "112") (name "/S_EXT_33<5>") (class "Default")
      (node (ref "J29") (pin "11") (pinfunction "11_11") (pintype "passive"))
      (node (ref "U22") (pin "9") (pinfunction "1B6_9") (pintype "bidirectional"))
    )
    (net (code "113") (name "/S_EXT_33<6>") (class "Default")
      (node (ref "J29") (pin "9") (pinfunction "9_9") (pintype "passive"))
      (node (ref "U22") (pin "11") (pinfunction "1B7_11") (pintype "bidirectional"))
    )
    (net (code "114") (name "/S_EXT_33<7>") (class "Default")
      (node (ref "J29") (pin "7") (pinfunction "7_7") (pintype "passive"))
      (node (ref "U22") (pin "12") (pinfunction "1B8_12") (pintype "bidirectional"))
    )
    (net (code "115") (name "/S_EXT_33<8>") (class "Default")
      (node (ref "J29") (pin "5") (pinfunction "5_5") (pintype "passive"))
      (node (ref "U22") (pin "13") (pinfunction "2B1_13") (pintype "bidirectional"))
    )
    (net (code "116") (name "/S_EXT_33<9>") (class "Default")
      (node (ref "J29") (pin "3") (pinfunction "3_3") (pintype "passive"))
      (node (ref "U22") (pin "14") (pinfunction "2B2_14") (pintype "bidirectional"))
    )
    (net (code "117") (name "/S_EXT_33<10>") (class "Default")
      (node (ref "J29") (pin "1") (pinfunction "1_1") (pintype "passive"))
      (node (ref "U22") (pin "16") (pinfunction "2B3_16") (pintype "bidirectional"))
    )
    (net (code "118") (name "/TSENSE") (class "Default")
      (node (ref "J14") (pin "4") (pinfunction "4_4") (pintype "passive"))
      (node (ref "J16") (pin "1") (pinfunction "1_1") (pintype "passive"))
      (node (ref "J22") (pin "19") (pinfunction "19_19") (pintype "passive"))
      (node (ref "U25") (pin "3") (pinfunction "CH2_3") (pintype "input"))
    )
    (net (code "119") (name "/VBLEED") (class "Default")
      (node (ref "U10") (pin "9") (pinfunction "VOUTA_9") (pintype "output"))
      (node (ref "U11") (pin "3") (pinfunction "IN+_3") (pintype "input"))
    )
    (net (code "120") (name "/VDDA_EXT") (class "Default")
      (node (ref "S2") (pin "5") (pinfunction "5_5") (pintype "passive"))
      (node (ref "U2") (pin "1") (pinfunction "CTL_1") (pintype "output"))
      (node (ref "U3") (pin "1") (pinfunction "CTL_1") (pintype "output"))
    )
    (net (code "121") (name "/VDDD_EXT") (class "Default")
      (node (ref "S1") (pin "5") (pinfunction "5_5") (pintype "passive"))
      (node (ref "U5") (pin "1") (pinfunction "CTL_1") (pintype "output"))
      (node (ref "U6") (pin "1") (pinfunction "CTL_1") (pintype "output"))
    )
    (net (code "122") (name "/VIL") (class "Default")
      (node (ref "J21") (pin "3") (pinfunction "3_3") (pintype "passive"))
      (node (ref "J25") (pin "1") (pinfunction "1_1") (pintype "passive"))
      (node (ref "U9") (pin "9") (pinfunction "VOUTA_9") (pintype "output"))
    )
    (net (code "123") (name "/VMODE_EXT") (class "Default")
      (node (ref "J24") (pin "7") (pinfunction "7_7") (pintype "passive"))
      (node (ref "S3") (pin "5") (pinfunction "5_5") (pintype "passive"))
    )
    (net (code "124") (name "/VPOS_AFE") (class "Default")
      (node (ref "J14") (pin "3") (pinfunction "3_3") (pintype "passive"))
      (node (ref "J15") (pin "1") (pinfunction "1_1") (pintype "passive"))
      (node (ref "J24") (pin "6") (pinfunction "6_6") (pintype "passive"))
      (node (ref "U25") (pin "4") (pinfunction "CH3_4") (pintype "input"))
    )
    (net (code "125") (name "/VPOS_CM") (class "Default")
      (node (ref "J21") (pin "10") (pinfunction "10_10") (pintype "passive"))
      (node (ref "J24") (pin "2") (pinfunction "2_2") (pintype "passive"))
      (node (ref "J26") (pin "3") (pinfunction "3_3") (pintype "passive"))
      (node (ref "U9") (pin "8") (pinfunction "VOUTB_8") (pintype "output"))
    )
    (net (code "126") (name "/VREFH") (class "Default")
      (node (ref "J21") (pin "11") (pinfunction "11_11") (pintype "passive"))
      (node (ref "J26") (pin "2") (pinfunction "2_2") (pintype "passive"))
      (node (ref "U9") (pin "3") (pinfunction "VOUTC_3") (pintype "output"))
    )
    (net (code "127") (name "/VREFL") (class "Default")
      (node (ref "J21") (pin "12") (pinfunction "12_12") (pintype "passive"))
      (node (ref "J26") (pin "1") (pinfunction "1_1") (pintype "passive"))
      (node (ref "U9") (pin "2") (pinfunction "VOUTD_2") (pintype "output"))
    )
    (net (code "128") (name "/VREF_2P5V") (class "Default")
      (node (ref "C23") (pin "1") (pintype "passive"))
      (node (ref "C31") (pin "1") (pintype "passive"))
      (node (ref "C46") (pin "1") (pintype "passive"))
      (node (ref "C73") (pin "1") (pintype "passive"))
      (node (ref "C74") (pin "1") (pintype "passive"))
      (node (ref "J33") (pin "1") (pinfunction "1_1") (pintype "passive"))
      (node (ref "U10") (pin "7") (pinfunction "VREFH_7") (pintype "input"))
      (node (ref "U17") (pin "7") (pinfunction "VREFH_7") (pintype "input"))
      (node (ref "U25") (pin "11") (pinfunction "VREF_11") (pintype "input"))
      (node (ref "U25") (pin "5") (pinfunction "CH4_5") (pintype "input"))
      (node (ref "U25") (pin "6") (pinfunction "CH5_6") (pintype "input"))
      (node (ref "U27") (pin "3") (pinfunction "IN+_3") (pintype "input"))
      (node (ref "U7") (pin "6") (pinfunction "VOUT_6") (pintype "output"))
      (node (ref "U9") (pin "7") (pinfunction "VREFH_7") (pintype "input"))
    )
    (net (code "129") (name "/VSLEW") (class "Default")
      (node (ref "U17") (pin "9") (pinfunction "VOUTA_9") (pintype "output"))
      (node (ref "U18") (pin "3") (pinfunction "IN+_3") (pintype "input"))
    )
    (net (code "130") (name "/VSPK") (class "Default")
      (node (ref "U17") (pin "8") (pinfunction "VOUTB_8") (pintype "output"))
      (node (ref "U20") (pin "3") (pinfunction "IN+_3") (pintype "input"))
    )
    (net (code "131") (name "/VSPKFAST") (class "Default")
      (node (ref "U17") (pin "3") (pinfunction "VOUTC_3") (pintype "output"))
      (node (ref "U23") (pin "3") (pinfunction "IN+_3") (pintype "input"))
    )
    (net (code "132") (name "/VTAIL") (class "Default")
      (node (ref "U10") (pin "3") (pinfunction "VOUTC_3") (pintype "output"))
      (node (ref "U15") (pin "3") (pinfunction "IN+_3") (pintype "input"))
    )
    (net (code "133") (name "/VTH") (class "Default")
      (node (ref "U10") (pin "8") (pinfunction "VOUTB_8") (pintype "output"))
      (node (ref "U13") (pin "3") (pinfunction "IN+_3") (pintype "input"))
    )
    (net (code "134") (name "AVDD") (class "Default")
      (node (ref "C8") (pin "1") (pinfunction "1_1") (pintype "passive"))
      (node (ref "J21") (pin "15") (pinfunction "15_15") (pintype "passive"))
      (node (ref "J21") (pin "2") (pinfunction "2_2") (pintype "passive"))
      (node (ref "J3") (pin "2") (pinfunction "2_2") (pintype "passive"))
      (node (ref "R3") (pin "1") (pinfunction "1_1") (pintype "passive"))
      (node (ref "U2") (pin "4") (pinfunction "VO_4") (pintype "output"))
    )
    (net (code "135") (name "DVDD") (class "Default")
      (node (ref "C12") (pin "1") (pinfunction "1_1") (pintype "passive"))
      (node (ref "J21") (pin "19") (pinfunction "19_19") (pintype "passive"))
      (node (ref "J22") (pin "1") (pinfunction "1_1") (pintype "passive"))
      (node (ref "J3") (pin "4") (pinfunction "4_4") (pintype "passive"))
      (node (ref "R5") (pin "1") (pinfunction "1_1") (pintype "passive"))
      (node (ref "U5") (pin "4") (pinfunction "VO_4") (pintype "output"))
    )
    (net (code "136") (name "GND") (class "Default")
      (node (ref "C1") (pin "-") (pinfunction "-_-") (pintype "passive"))
      (node (ref "C10") (pin "2") (pinfunction "2_2") (pintype "passive"))
      (node (ref "C11") (pin "2") (pinfunction "2_2") (pintype "passive"))
      (node (ref "C12") (pin "2") (pinfunction "2_2") (pintype "passive"))
      (node (ref "C13") (pin "2") (pinfunction "2_2") (pintype "passive"))
      (node (ref "C14") (pin "2") (pinfunction "2_2") (pintype "passive"))
      (node (ref "C15") (pin "2") (pintype "passive"))
      (node (ref "C16") (pin "2") (pintype "passive"))
      (node (ref "C17") (pin "2") (pintype "passive"))
      (node (ref "C18") (pin "2") (pintype "passive"))
      (node (ref "C19") (pin "2") (pintype "passive"))
      (node (ref "C2") (pin "-") (pinfunction "-_-") (pintype "passive"))
      (node (ref "C20") (pin "2") (pintype "passive"))
      (node (ref "C21") (pin "2") (pintype "passive"))
      (node (ref "C22") (pin "2") (pintype "passive"))
      (node (ref "C23") (pin "2") (pintype "passive"))
      (node (ref "C24") (pin "2") (pintype "passive"))
      (node (ref "C25") (pin "2") (pintype "passive"))
      (node (ref "C26") (pin "2") (pintype "passive"))
      (node (ref "C27") (pin "2") (pintype "passive"))
      (node (ref "C28") (pin "2") (pintype "passive"))
      (node (ref "C29") (pin "2") (pintype "passive"))
      (node (ref "C3") (pin "2") (pinfunction "2_2") (pintype "passive"))
      (node (ref "C31") (pin "2") (pintype "passive"))
      (node (ref "C32") (pin "2") (pintype "passive"))
      (node (ref "C33") (pin "2") (pintype "passive"))
      (node (ref "C34") (pin "2") (pintype "passive"))
      (node (ref "C35") (pin "2") (pintype "passive"))
      (node (ref "C37") (pin "2") (pintype "passive"))
      (node (ref "C38") (pin "2") (pintype "passive"))
      (node (ref "C39") (pin "2") (pintype "passive"))
      (node (ref "C4") (pin "2") (pinfunction "2_2") (pintype "passive"))
      (node (ref "C40") (pin "2") (pintype "passive"))
      (node (ref "C42") (pin "2") (pintype "passive"))
      (node (ref "C43") (pin "2") (pintype "passive"))
      (node (ref "C44") (pin "2") (pintype "passive"))
      (node (ref "C45") (pin "2") (pintype "passive"))
      (node (ref "C46") (pin "2") (pintype "passive"))
      (node (ref "C47") (pin "2") (pintype "passive"))
      (node (ref "C48") (pin "2") (pintype "passive"))
      (node (ref "C5") (pin "2") (pinfunction "2_2") (pintype "passive"))
      (node (ref "C50") (pin "2") (pintype "passive"))
      (node (ref "C51") (pin "2") (pintype "passive"))
      (node (ref "C52") (pin "2") (pintype "passive"))
      (node (ref "C53") (pin "2") (pintype "passive"))
      (node (ref "C54") (pin "2") (pintype "passive"))
      (node (ref "C55") (pin "2") (pintype "passive"))
      (node (ref "C56") (pin "2") (pintype "passive"))
      (node (ref "C57") (pin "2") (pintype "passive"))
      (node (ref "C59") (pin "2") (pintype "passive"))
      (node (ref "C6") (pin "2") (pinfunction "2_2") (pintype "passive"))
      (node (ref "C60") (pin "2") (pintype "passive"))
      (node (ref "C61") (pin "2") (pintype "passive"))
      (node (ref "C62") (pin "2") (pintype "passive"))
      (node (ref "C64") (pin "2") (pintype "passive"))
      (node (ref "C65") (pin "2") (pintype "passive"))
      (node (ref "C66") (pin "2") (pintype "passive"))
      (node (ref "C67") (pin "2") (pintype "passive"))
      (node (ref "C68") (pin "2") (pintype "passive"))
      (node (ref "C69") (pin "2") (pintype "passive"))
      (node (ref "C7") (pin "2") (pinfunction "2_2") (pintype "passive"))
      (node (ref "C72") (pin "2") (pintype "passive"))
      (node (ref "C73") (pin "2") (pintype "passive"))
      (node (ref "C74") (pin "2") (pintype "passive"))
      (node (ref "C8") (pin "2") (pinfunction "2_2") (pintype "passive"))
      (node (ref "C9") (pin "2") (pinfunction "2_2") (pintype "passive"))
      (node (ref "J2") (pin "1") (pinfunction "1_1") (pintype "passive"))
      (node (ref "J21") (pin "13") (pinfunction "13_13") (pintype "passive"))
      (node (ref "J22") (pin "17") (pinfunction "17_17") (pintype "passive"))
      (node (ref "J22") (pin "18") (pinfunction "18_18") (pintype "passive"))
      (node (ref "J22") (pin "2") (pinfunction "2_2") (pintype "passive"))
      (node (ref "J22") (pin "4") (pinfunction "4_4") (pintype "passive"))
      (node (ref "J5") (pin "1") (pinfunction "1_1") (pintype "passive"))
      (node (ref "R10") (pin "2") (pinfunction "2_2") (pintype "passive"))
      (node (ref "R2") (pin "2") (pinfunction "2_2") (pintype "passive"))
      (node (ref "R21") (pin "2") (pinfunction "2_2") (pintype "passive"))
      (node (ref "R7") (pin "2") (pinfunction "2_2") (pintype "passive"))
      (node (ref "R8") (pin "2") (pinfunction "2_2") (pintype "passive"))
      (node (ref "R9") (pin "2") (pinfunction "2_2") (pintype "passive"))
      (node (ref "S1") (pin "1") (pinfunction "1_1") (pintype "passive"))
      (node (ref "S1") (pin "2") (pinfunction "2_2") (pintype "passive"))
      (node (ref "S1") (pin "3") (pinfunction "3_3") (pintype "passive"))
      (node (ref "S1") (pin "4") (pinfunction "4_4") (pintype "passive"))
      (node (ref "S2") (pin "1") (pinfunction "1_1") (pintype "passive"))
      (node (ref "S2") (pin "2") (pinfunction "2_2") (pintype "passive"))
      (node (ref "S2") (pin "3") (pinfunction "3_3") (pintype "passive"))
      (node (ref "S2") (pin "4") (pinfunction "4_4") (pintype "passive"))
      (node (ref "S3") (pin "1") (pinfunction "1_1") (pintype "passive"))
      (node (ref "S3") (pin "2") (pinfunction "2_2") (pintype "passive"))
      (node (ref "S3") (pin "3") (pinfunction "3_3") (pintype "passive"))
      (node (ref "S3") (pin "4") (pinfunction "4_4") (pintype "passive"))
      (node (ref "S4") (pin "1") (pinfunction "1_1") (pintype "passive"))
      (node (ref "S4") (pin "2") (pinfunction "2_2") (pintype "passive"))
      (node (ref "S4") (pin "3") (pinfunction "3_3") (pintype "passive"))
      (node (ref "S4") (pin "4") (pinfunction "4_4") (pintype "passive"))
      (node (ref "S5") (pin "1") (pinfunction "1_1") (pintype "passive"))
      (node (ref "S5") (pin "2") (pinfunction "2_2") (pintype "passive"))
      (node (ref "S5") (pin "3") (pinfunction "3_3") (pintype "passive"))
      (node (ref "S5") (pin "4") (pinfunction "4_4") (pintype "passive"))
      (node (ref "U1") (pin "3") (pinfunction "GND_3") (pintype "passive"))
      (node (ref "U1") (pin "5") (pinfunction "~ERROR_5") (pintype "passive"))
      (node (ref "U1") (pin "6") (pinfunction "16_6") (pintype "passive"))
      (node (ref "U10") (pin "10") (pinfunction "VSS_10") (pintype "power_in"))
      (node (ref "U10") (pin "11") (pinfunction "GND_11") (pintype "power_in"))
      (node (ref "U10") (pin "20") (pinfunction "RESETSEL_20") (pintype "passive"))
      (node (ref "U10") (pin "4") (pinfunction "VREFL_4") (pintype "input"))
      (node (ref "U11") (pin "2") (pinfunction "GND_2") (pintype "power_in"))
      (node (ref "U13") (pin "2") (pinfunction "GND_2") (pintype "power_in"))
      (node (ref "U15") (pin "2") (pinfunction "GND_2") (pintype "power_in"))
      (node (ref "U17") (pin "10") (pinfunction "VSS_10") (pintype "power_in"))
      (node (ref "U17") (pin "11") (pinfunction "GND_11") (pintype "power_in"))
      (node (ref "U17") (pin "20") (pinfunction "RESETSEL_20") (pintype "passive"))
      (node (ref "U17") (pin "4") (pinfunction "VREFL_4") (pintype "input"))
      (node (ref "U18") (pin "2") (pinfunction "GND_2") (pintype "power_in"))
      (node (ref "U2") (pin "3") (pinfunction "GND_3") (pintype "passive"))
      (node (ref "U2") (pin "6") (pinfunction "FIN_6") (pintype "passive"))
      (node (ref "U20") (pin "2") (pinfunction "GND_2") (pintype "power_in"))
      (node (ref "U22") (pin "1") (pinfunction "1DIR_1") (pintype "input"))
      (node (ref "U22") (pin "10") (pinfunction "GND_10") (pintype "power_in"))
      (node (ref "U22") (pin "15") (pinfunction "GND_15") (pintype "power_in"))
      (node (ref "U22") (pin "17") (pinfunction "2B4_17") (pintype "bidirectional"))
      (node (ref "U22") (pin "19") (pinfunction "2B5_19") (pintype "bidirectional"))
      (node (ref "U22") (pin "20") (pinfunction "2B6_20") (pintype "bidirectional"))
      (node (ref "U22") (pin "21") (pinfunction "GND_21") (pintype "power_in"))
      (node (ref "U22") (pin "22") (pinfunction "2B7_22") (pintype "bidirectional"))
      (node (ref "U22") (pin "23") (pinfunction "2B8_23") (pintype "bidirectional"))
      (node (ref "U22") (pin "24") (pinfunction "2DIR_24") (pintype "input"))
      (node (ref "U22") (pin "25") (pinfunction "*2OE_25") (pintype "input"))
      (node (ref "U22") (pin "28") (pinfunction "GND_28") (pintype "power_in"))
      (node (ref "U22") (pin "34") (pinfunction "GND_34") (pintype "power_in"))
      (node (ref "U22") (pin "39") (pinfunction "GND_39") (pintype "power_in"))
      (node (ref "U22") (pin "4") (pinfunction "GND_4") (pintype "power_in"))
      (node (ref "U22") (pin "45") (pinfunction "GND_45") (pintype "power_in"))
      (node (ref "U22") (pin "48") (pinfunction "*1OE_48") (pintype "input"))
      (node (ref "U23") (pin "2") (pinfunction "GND_2") (pintype "power_in"))
      (node (ref "U25") (pin "13") (pinfunction "GND_13") (pintype "power_in"))
      (node (ref "U25") (pin "14") (pinfunction "GND_14") (pintype "power_in"))
      (node (ref "U25") (pin "7") (pinfunction "CH6_7") (pintype "input"))
      (node (ref "U25") (pin "8") (pinfunction "CH7_8") (pintype "input"))
      (node (ref "U25") (pin "9") (pinfunction "COM_9") (pintype "input"))
      (node (ref "U26") (pin "2") (pinfunction "GND_2") (pintype "power_in"))
      (node (ref "U27") (pin "4") (pinfunction "V-_4") (pintype "power_in"))
      (node (ref "U3") (pin "3") (pinfunction "GND_3") (pintype "passive"))
      (node (ref "U3") (pin "6") (pinfunction "FIN_6") (pintype "passive"))
      (node (ref "U4") (pin "2") (pinfunction "N.C._2") (pintype "passive"))
      (node (ref "U5") (pin "3") (pinfunction "GND_3") (pintype "passive"))
      (node (ref "U5") (pin "6") (pinfunction "FIN_6") (pintype "passive"))
      (node (ref "U6") (pin "3") (pinfunction "GND_3") (pintype "passive"))
      (node (ref "U6") (pin "6") (pinfunction "FIN_6") (pintype "passive"))
      (node (ref "U7") (pin "4") (pinfunction "GND_4") (pintype "passive"))
      (node (ref "U8") (pin "1") (pinfunction "1DIR_1") (pintype "input"))
      (node (ref "U8") (pin "10") (pinfunction "GND_10") (pintype "power_in"))
      (node (ref "U8") (pin "15") (pinfunction "GND_15") (pintype "power_in"))
      (node (ref "U8") (pin "21") (pinfunction "GND_21") (pintype "power_in"))
      (node (ref "U8") (pin "23") (pinfunction "2B8_23") (pintype "bidirectional"))
      (node (ref "U8") (pin "24") (pinfunction "2DIR_24") (pintype "input"))
      (node (ref "U8") (pin "25") (pinfunction "*2OE_25") (pintype "input"))
      (node (ref "U8") (pin "28") (pinfunction "GND_28") (pintype "power_in"))
      (node (ref "U8") (pin "34") (pinfunction "GND_34") (pintype "power_in"))
      (node (ref "U8") (pin "39") (pinfunction "GND_39") (pintype "power_in"))
      (node (ref "U8") (pin "4") (pinfunction "GND_4") (pintype "power_in"))
      (node (ref "U8") (pin "45") (pinfunction "GND_45") (pintype "power_in"))
      (node (ref "U8") (pin "48") (pinfunction "*1OE_48") (pintype "input"))
      (node (ref "U9") (pin "10") (pinfunction "VSS_10") (pintype "power_in"))
      (node (ref "U9") (pin "11") (pinfunction "GND_11") (pintype "power_in"))
      (node (ref "U9") (pin "20") (pinfunction "RESETSEL_20") (pintype "passive"))
      (node (ref "U9") (pin "4") (pinfunction "VREFL_4") (pintype "input"))
    )
    (net (code "137") (name "LCVDD") (class "Default")
      (node (ref "C10") (pin "1") (pinfunction "1_1") (pintype "passive"))
      (node (ref "J21") (pin "16") (pinfunction "16_16") (pintype "passive"))
      (node (ref "J3") (pin "1") (pinfunction "1_1") (pintype "passive"))
      (node (ref "R4") (pin "1") (pinfunction "1_1") (pintype "passive"))
      (node (ref "U3") (pin "4") (pinfunction "VO_4") (pintype "output"))
    )
    (net (code "138") (name "Net-(R2-Pad1)") (class "Default")
      (node (ref "R2") (pin "1") (pinfunction "1_1") (pintype "passive"))
      (node (ref "VDD_1") (pin "K") (pinfunction "K_K") (pintype "passive"))
    )
    (net (code "139") (name "Net-(U1-~SD)") (class "Default")
      (node (ref "R1") (pin "1") (pinfunction "1_1") (pintype "passive"))
      (node (ref "U1") (pin "1") (pinfunction "~SD_1") (pintype "passive"))
    )
    (net (code "140") (name "Net-(U2-ADJ)") (class "Default")
      (node (ref "R3") (pin "2") (pinfunction "2_2") (pintype "passive"))
      (node (ref "R7") (pin "1") (pinfunction "1_1") (pintype "passive"))
      (node (ref "U2") (pin "5") (pinfunction "ADJ_5") (pintype "bidirectional"))
    )
    (net (code "141") (name "Net-(U3-ADJ)") (class "Default")
      (node (ref "R4") (pin "2") (pinfunction "2_2") (pintype "passive"))
      (node (ref "R8") (pin "1") (pinfunction "1_1") (pintype "passive"))
      (node (ref "U3") (pin "5") (pinfunction "ADJ_5") (pintype "bidirectional"))
    )
    (net (code "142") (name "Net-(U5-ADJ)") (class "Default")
      (node (ref "R5") (pin "2") (pinfunction "2_2") (pintype "passive"))
      (node (ref "R9") (pin "1") (pinfunction "1_1") (pintype "passive"))
      (node (ref "U5") (pin "5") (pinfunction "ADJ_5") (pintype "bidirectional"))
    )
    (net (code "143") (name "Net-(U6-ADJ)") (class "Default")
      (node (ref "R10") (pin "1") (pinfunction "1_1") (pintype "passive"))
      (node (ref "R6") (pin "2") (pinfunction "2_2") (pintype "passive"))
      (node (ref "U6") (pin "5") (pinfunction "ADJ_5") (pintype "bidirectional"))
    )
    (net (code "144") (name "Net-(U11-IN-)") (class "Default")
      (node (ref "C30") (pin "1") (pintype "passive"))
      (node (ref "R11") (pin "2") (pinfunction "2_2") (pintype "passive"))
      (node (ref "U11") (pin "4") (pinfunction "IN-_4") (pintype "input"))
      (node (ref "U12") (pin "2") (pinfunction "EMITTER_2") (pintype "passive"))
    )
    (net (code "145") (name "Net-(U11-OUT)") (class "Default")
      (node (ref "C30") (pin "2") (pintype "passive"))
      (node (ref "U11") (pin "1") (pinfunction "OUT_1") (pintype "output"))
      (node (ref "U12") (pin "1") (pinfunction "BASE_1") (pintype "passive"))
    )
    (net (code "146") (name "Net-(U13-IN-)") (class "Default")
      (node (ref "C36") (pin "1") (pintype "passive"))
      (node (ref "R12") (pin "2") (pinfunction "2_2") (pintype "passive"))
      (node (ref "U13") (pin "4") (pinfunction "IN-_4") (pintype "input"))
      (node (ref "U14") (pin "2") (pinfunction "EMITTER_2") (pintype "passive"))
    )
    (net (code "147") (name "Net-(U13-OUT)") (class "Default")
      (node (ref "C36") (pin "2") (pintype "passive"))
      (node (ref "U13") (pin "1") (pinfunction "OUT_1") (pintype "output"))
      (node (ref "U14") (pin "1") (pinfunction "BASE_1") (pintype "passive"))
    )
    (net (code "148") (name "Net-(U15-IN-)") (class "Default")
      (node (ref "C41") (pin "1") (pintype "passive"))
      (node (ref "R13") (pin "2") (pinfunction "2_2") (pintype "passive"))
      (node (ref "U15") (pin "4") (pinfunction "IN-_4") (pintype "input"))
      (node (ref "U16") (pin "2") (pinfunction "EMITTER_2") (pintype "passive"))
    )
    (net (code "149") (name "Net-(U15-OUT)") (class "Default")
      (node (ref "C41") (pin "2") (pintype "passive"))
      (node (ref "U15") (pin "1") (pinfunction "OUT_1") (pintype "output"))
      (node (ref "U16") (pin "1") (pinfunction "BASE_1") (pintype "passive"))
    )
    (net (code "150") (name "Net-(U18-IN-)") (class "Default")
      (node (ref "C49") (pin "1") (pintype "passive"))
      (node (ref "R14") (pin "2") (pinfunction "2_2") (pintype "passive"))
      (node (ref "U18") (pin "4") (pinfunction "IN-_4") (pintype "input"))
      (node (ref "U19") (pin "2") (pinfunction "EMITTER_2") (pintype "passive"))
    )
    (net (code "151") (name "Net-(U18-OUT)") (class "Default")
      (node (ref "C49") (pin "2") (pintype "passive"))
      (node (ref "U18") (pin "1") (pinfunction "OUT_1") (pintype "output"))
      (node (ref "U19") (pin "1") (pinfunction "BASE_1") (pintype "passive"))
    )
    (net (code "152") (name "Net-(U20-IN-)") (class "Default")
      (node (ref "C58") (pin "1") (pintype "passive"))
      (node (ref "R15") (pin "2") (pinfunction "2_2") (pintype "passive"))
      (node (ref "U20") (pin "4") (pinfunction "IN-_4") (pintype "input"))
      (node (ref "U21") (pin "2") (pinfunction "EMITTER_2") (pintype "passive"))
    )
    (net (code "153") (name "Net-(U20-OUT)") (class "Default")
      (node (ref "C58") (pin "2") (pintype "passive"))
      (node (ref "U20") (pin "1") (pinfunction "OUT_1") (pintype "output"))
      (node (ref "U21") (pin "1") (pinfunction "BASE_1") (pintype "passive"))
    )
    (net (code "154") (name "Net-(U23-IN-)") (class "Default")
      (node (ref "C63") (pin "1") (pintype "passive"))
      (node (ref "R16") (pin "2") (pinfunction "2_2") (pintype "passive"))
      (node (ref "U23") (pin "4") (pinfunction "IN-_4") (pintype "input"))
      (node (ref "U24") (pin "2") (pinfunction "EMITTER_2") (pintype "passive"))
    )
    (net (code "155") (name "Net-(U23-OUT)") (class "Default")
      (node (ref "C63") (pin "2") (pintype "passive"))
      (node (ref "U23") (pin "1") (pinfunction "OUT_1") (pintype "output"))
      (node (ref "U24") (pin "1") (pinfunction "BASE_1") (pintype "passive"))
    )
    (net (code "156") (name "Net-(U26-IN+)") (class "Default")
      (node (ref "C72") (pin "1") (pintype "passive"))
      (node (ref "R20") (pin "2") (pinfunction "2_2") (pintype "passive"))
      (node (ref "R21") (pin "1") (pinfunction "1_1") (pintype "passive"))
      (node (ref "U26") (pin "3") (pinfunction "IN+_3") (pintype "input"))
    )
    (net (code "157") (name "Net-(U26-IN-)") (class "Default")
      (node (ref "C71") (pin "2") (pinfunction "2_2") (pintype "passive"))
      (node (ref "R17") (pin "1") (pinfunction "1_1") (pintype "passive"))
      (node (ref "R19") (pin "2") (pinfunction "2_2") (pintype "passive"))
      (node (ref "U26") (pin "4") (pinfunction "IN-_4") (pintype "input"))
    )
    (net (code "158") (name "VDD") (class "Default")
      (node (ref "C14") (pin "1") (pinfunction "1_1") (pintype "passive"))
      (node (ref "J21") (pin "17") (pinfunction "17_17") (pintype "passive"))
      (node (ref "J22") (pin "20") (pinfunction "20_20") (pintype "passive"))
      (node (ref "J3") (pin "3") (pinfunction "3_3") (pintype "passive"))
      (node (ref "R6") (pin "1") (pinfunction "1_1") (pintype "passive"))
      (node (ref "U6") (pin "4") (pinfunction "VO_4") (pintype "output"))
    )
    (net (code "159") (name "VDDPST") (class "Default")
      (node (ref "C1") (pin "+") (pinfunction "+_+") (pintype "passive"))
      (node (ref "J21") (pin "18") (pinfunction "18_18") (pintype "passive"))
      (node (ref "J22") (pin "15") (pinfunction "15_15") (pintype "passive"))
      (node (ref "J6") (pin "1") (pinfunction "1_1") (pintype "passive"))
      (node (ref "L1") (pin "1") (pinfunction "1_1") (pintype "passive"))
    )
    (net (code "160") (name "VDD_2P5V") (class "Default")
      (node (ref "C28") (pin "1") (pintype "passive"))
      (node (ref "C29") (pin "1") (pintype "passive"))
      (node (ref "C34") (pin "1") (pintype "passive"))
      (node (ref "C35") (pin "1") (pintype "passive"))
      (node (ref "C39") (pin "1") (pintype "passive"))
      (node (ref "C40") (pin "1") (pintype "passive"))
      (node (ref "C47") (pin "1") (pintype "passive"))
      (node (ref "C48") (pin "1") (pintype "passive"))
      (node (ref "C52") (pin "1") (pintype "passive"))
      (node (ref "C53") (pin "1") (pintype "passive"))
      (node (ref "C6") (pin "1") (pinfunction "1_1") (pintype "passive"))
      (node (ref "C61") (pin "1") (pintype "passive"))
      (node (ref "C62") (pin "1") (pintype "passive"))
      (node (ref "J8") (pin "1") (pinfunction "1_1") (pintype "passive"))
      (node (ref "R11") (pin "1") (pinfunction "1_1") (pintype "passive"))
      (node (ref "R12") (pin "1") (pinfunction "1_1") (pintype "passive"))
      (node (ref "R13") (pin "1") (pinfunction "1_1") (pintype "passive"))
      (node (ref "R14") (pin "1") (pinfunction "1_1") (pintype "passive"))
      (node (ref "R15") (pin "1") (pinfunction "1_1") (pintype "passive"))
      (node (ref "R16") (pin "1") (pinfunction "1_1") (pintype "passive"))
      (node (ref "R20") (pin "1") (pinfunction "1_1") (pintype "passive"))
      (node (ref "U1") (pin "4") (pinfunction "Vout_4") (pintype "output"))
    )
    (net (code "161") (name "VDD_5V_IN") (class "Default")
      (node (ref "C11") (pin "1") (pinfunction "1_1") (pintype "passive"))
      (node (ref "C13") (pin "1") (pinfunction "1_1") (pintype "passive"))
      (node (ref "C15") (pin "1") (pintype "passive"))
      (node (ref "C16") (pin "1") (pintype "passive"))
      (node (ref "C17") (pin "1") (pintype "passive"))
      (node (ref "C18") (pin "1") (pintype "passive"))
      (node (ref "C2") (pin "+") (pinfunction "+_+") (pintype "passive"))
      (node (ref "C21") (pin "1") (pintype "passive"))
      (node (ref "C22") (pin "1") (pintype "passive"))
      (node (ref "C24") (pin "1") (pintype "passive"))
      (node (ref "C25") (pin "1") (pintype "passive"))
      (node (ref "C26") (pin "1") (pintype "passive"))
      (node (ref "C27") (pin "1") (pintype "passive"))
      (node (ref "C3") (pin "1") (pinfunction "1_1") (pintype "passive"))
      (node (ref "C32") (pin "1") (pintype "passive"))
      (node (ref "C33") (pin "1") (pintype "passive"))
      (node (ref "C37") (pin "1") (pintype "passive"))
      (node (ref "C38") (pin "1") (pintype "passive"))
      (node (ref "C4") (pin "1") (pinfunction "1_1") (pintype "passive"))
      (node (ref "C42") (pin "1") (pintype "passive"))
      (node (ref "C43") (pin "1") (pintype "passive"))
      (node (ref "C44") (pin "1") (pintype "passive"))
      (node (ref "C45") (pin "1") (pintype "passive"))
      (node (ref "C50") (pin "1") (pintype "passive"))
      (node (ref "C51") (pin "1") (pintype "passive"))
      (node (ref "C54") (pin "1") (pintype "passive"))
      (node (ref "C55") (pin "1") (pintype "passive"))
      (node (ref "C59") (pin "1") (pintype "passive"))
      (node (ref "C60") (pin "1") (pintype "passive"))
      (node (ref "C64") (pin "1") (pintype "passive"))
      (node (ref "C65") (pin "1") (pintype "passive"))
      (node (ref "C66") (pin "1") (pintype "passive"))
      (node (ref "C67") (pin "1") (pintype "passive"))
      (node (ref "C68") (pin "1") (pintype "passive"))
      (node (ref "C69") (pin "1") (pintype "passive"))
      (node (ref "C7") (pin "1") (pinfunction "1_1") (pintype "passive"))
      (node (ref "C9") (pin "1") (pinfunction "1_1") (pintype "passive"))
      (node (ref "J1") (pin "1") (pinfunction "1_1") (pintype "passive"))
      (node (ref "J4") (pin "1") (pinfunction "1_1") (pintype "passive"))
      (node (ref "L1") (pin "2") (pinfunction "2_2") (pintype "passive"))
      (node (ref "R1") (pin "2") (pinfunction "2_2") (pintype "passive"))
      (node (ref "S1") (pin "6") (pinfunction "6_6") (pintype "passive"))
      (node (ref "S2") (pin "6") (pinfunction "6_6") (pintype "passive"))
      (node (ref "S3") (pin "6") (pinfunction "6_6") (pintype "passive"))
      (node (ref "S4") (pin "6") (pinfunction "6_6") (pintype "passive"))
      (node (ref "U1") (pin "2") (pinfunction "Vin_2") (pintype "input"))
      (node (ref "U10") (pin "1") (pinfunction "VDD_1") (pintype "power_in"))
      (node (ref "U11") (pin "5") (pinfunction "VDD_5") (pintype "power_in"))
      (node (ref "U13") (pin "5") (pinfunction "VDD_5") (pintype "power_in"))
      (node (ref "U15") (pin "5") (pinfunction "VDD_5") (pintype "power_in"))
      (node (ref "U17") (pin "1") (pinfunction "VDD_1") (pintype "power_in"))
      (node (ref "U18") (pin "5") (pinfunction "VDD_5") (pintype "power_in"))
      (node (ref "U2") (pin "2") (pinfunction "VCC_2") (pintype "power_in"))
      (node (ref "U20") (pin "5") (pinfunction "VDD_5") (pintype "power_in"))
      (node (ref "U22") (pin "31") (pinfunction "VCCA_31") (pintype "power_in"))
      (node (ref "U22") (pin "42") (pinfunction "VCCA_42") (pintype "power_in"))
      (node (ref "U23") (pin "5") (pinfunction "VDD_5") (pintype "power_in"))
      (node (ref "U25") (pin "10") (pinfunction "*SHDN_10") (pintype "passive"))
      (node (ref "U25") (pin "12") (pinfunction "VCC+_12") (pintype "power_in"))
      (node (ref "U25") (pin "20") (pinfunction "VCC+_20") (pintype "power_in"))
      (node (ref "U26") (pin "5") (pinfunction "VDD_5") (pintype "power_in"))
      (node (ref "U27") (pin "7") (pinfunction "V+_7") (pintype "power_in"))
      (node (ref "U3") (pin "2") (pinfunction "VCC_2") (pintype "power_in"))
      (node (ref "U4") (pin "1") (pinfunction "Vcc_1") (pintype "power_in"))
      (node (ref "U5") (pin "2") (pinfunction "VCC_2") (pintype "power_in"))
      (node (ref "U6") (pin "2") (pinfunction "VCC_2") (pintype "power_in"))
      (node (ref "U7") (pin "2") (pinfunction "VIN_2") (pintype "input"))
      (node (ref "U8") (pin "31") (pinfunction "VCCA_31") (pintype "power_in"))
      (node (ref "U8") (pin "42") (pinfunction "VCCA_42") (pintype "power_in"))
      (node (ref "U9") (pin "1") (pinfunction "VDD_1") (pintype "power_in"))
      (node (ref "VDD_1") (pin "A") (pinfunction "A_A") (pintype "passive"))
    )
    (net (code "162") (name "VDD_FPGA") (class "Default")
      (node (ref "C19") (pin "1") (pintype "passive"))
      (node (ref "C20") (pin "1") (pintype "passive"))
      (node (ref "C5") (pin "1") (pinfunction "1_1") (pintype "passive"))
      (node (ref "C56") (pin "1") (pintype "passive"))
      (node (ref "C57") (pin "1") (pintype "passive"))
      (node (ref "J7") (pin "1") (pinfunction "1_1") (pintype "passive"))
      (node (ref "U22") (pin "18") (pinfunction "VCCB_18") (pintype "power_in"))
      (node (ref "U22") (pin "7") (pinfunction "VCCB_7") (pintype "power_in"))
      (node (ref "U4") (pin "3") (pinfunction "Vo_3") (pintype "passive"))
      (node (ref "U8") (pin "18") (pinfunction "VCCB_18") (pintype "power_in"))
      (node (ref "U8") (pin "7") (pinfunction "VCCB_7") (pintype "power_in"))
    )
    (net (code "163") (name "unconnected-(J21-Pad1)") (class "Default")
      (node (ref "J21") (pin "1") (pinfunction "1_1") (pintype "passive"))
    )
    (net (code "164") (name "unconnected-(J21-Pad21)") (class "Default")
      (node (ref "J21") (pin "21") (pinfunction "21_21") (pintype "passive"))
    )
    (net (code "165") (name "unconnected-(J22-Pad22)") (class "Default")
      (node (ref "J22") (pin "22") (pinfunction "22_22") (pintype "passive"))
    )
    (net (code "166") (name "unconnected-(U7-DNC-Pad1)") (class "Default")
      (node (ref "U7") (pin "1") (pinfunction "DNC_1") (pintype "passive"))
    )
    (net (code "167") (name "unconnected-(U7-DNC-Pad8)") (class "Default")
      (node (ref "U7") (pin "8") (pinfunction "DNC_8") (pintype "passive"))
    )
    (net (code "168") (name "unconnected-(U7-NC-Pad7)") (class "Default")
      (node (ref "U7") (pin "7") (pinfunction "NC_7") (pintype "passive"))
    )
    (net (code "169") (name "unconnected-(U7-TEMP-Pad3)") (class "Default")
      (node (ref "U7") (pin "3") (pinfunction "TEMP_3") (pintype "passive"))
    )
    (net (code "170") (name "unconnected-(U7-TRIM{slash}NR-Pad5)") (class "Default")
      (node (ref "U7") (pin "5") (pinfunction "TRIM/NR_5") (pintype "passive"))
    )
    (net (code "171") (name "unconnected-(U8-2A8-Pad26)") (class "Default")
      (node (ref "U8") (pin "26") (pinfunction "2A8_26") (pintype "bidirectional"))
    )
    (net (code "172") (name "unconnected-(U9-NIC-Pad5)") (class "Default")
      (node (ref "U9") (pin "5") (pinfunction "NIC_5") (pintype "passive"))
    )
    (net (code "173") (name "unconnected-(U9-NIC-Pad6)") (class "Default")
      (node (ref "U9") (pin "6") (pinfunction "NIC_6") (pintype "passive"))
    )
    (net (code "174") (name "unconnected-(U9-NIC-Pad15)") (class "Default")
      (node (ref "U9") (pin "15") (pinfunction "NIC_15") (pintype "passive"))
    )
    (net (code "175") (name "unconnected-(U9-NIC-Pad16)") (class "Default")
      (node (ref "U9") (pin "16") (pinfunction "NIC_16") (pintype "passive"))
    )
    (net (code "176") (name "unconnected-(U9-NIC-Pad17)") (class "Default")
      (node (ref "U9") (pin "17") (pinfunction "NIC_17") (pintype "passive"))
    )
    (net (code "177") (name "unconnected-(U10-NIC-Pad5)") (class "Default")
      (node (ref "U10") (pin "5") (pinfunction "NIC_5") (pintype "passive"))
    )
    (net (code "178") (name "unconnected-(U10-NIC-Pad6)") (class "Default")
      (node (ref "U10") (pin "6") (pinfunction "NIC_6") (pintype "passive"))
    )
    (net (code "179") (name "unconnected-(U10-NIC-Pad15)") (class "Default")
      (node (ref "U10") (pin "15") (pinfunction "NIC_15") (pintype "passive"))
    )
    (net (code "180") (name "unconnected-(U10-NIC-Pad16)") (class "Default")
      (node (ref "U10") (pin "16") (pinfunction "NIC_16") (pintype "passive"))
    )
    (net (code "181") (name "unconnected-(U10-NIC-Pad17)") (class "Default")
      (node (ref "U10") (pin "17") (pinfunction "NIC_17") (pintype "passive"))
    )
    (net (code "182") (name "unconnected-(U10-VOUTD-Pad2)") (class "Default")
      (node (ref "U10") (pin "2") (pinfunction "VOUTD_2") (pintype "output"))
    )
    (net (code "183") (name "unconnected-(U17-NIC-Pad5)") (class "Default")
      (node (ref "U17") (pin "5") (pinfunction "NIC_5") (pintype "passive"))
    )
    (net (code "184") (name "unconnected-(U17-NIC-Pad6)") (class "Default")
      (node (ref "U17") (pin "6") (pinfunction "NIC_6") (pintype "passive"))
    )
    (net (code "185") (name "unconnected-(U17-NIC-Pad15)") (class "Default")
      (node (ref "U17") (pin "15") (pinfunction "NIC_15") (pintype "passive"))
    )
    (net (code "186") (name "unconnected-(U17-NIC-Pad16)") (class "Default")
      (node (ref "U17") (pin "16") (pinfunction "NIC_16") (pintype "passive"))
    )
    (net (code "187") (name "unconnected-(U17-NIC-Pad17)") (class "Default")
      (node (ref "U17") (pin "17") (pinfunction "NIC_17") (pintype "passive"))
    )
    (net (code "188") (name "unconnected-(U17-VOUTD-Pad2)") (class "Default")
      (node (ref "U17") (pin "2") (pinfunction "VOUTD_2") (pintype "output"))
    )
    (net (code "189") (name "unconnected-(U22-2A4-Pad32)") (class "Default")
      (node (ref "U22") (pin "32") (pinfunction "2A4_32") (pintype "bidirectional"))
    )
    (net (code "190") (name "unconnected-(U22-2A5-Pad30)") (class "Default")
      (node (ref "U22") (pin "30") (pinfunction "2A5_30") (pintype "bidirectional"))
    )
    (net (code "191") (name "unconnected-(U22-2A6-Pad29)") (class "Default")
      (node (ref "U22") (pin "29") (pinfunction "2A6_29") (pintype "bidirectional"))
    )
    (net (code "192") (name "unconnected-(U22-2A7-Pad27)") (class "Default")
      (node (ref "U22") (pin "27") (pinfunction "2A7_27") (pintype "bidirectional"))
    )
    (net (code "193") (name "unconnected-(U22-2A8-Pad26)") (class "Default")
      (node (ref "U22") (pin "26") (pinfunction "2A8_26") (pintype "bidirectional"))
    )
    (net (code "194") (name "unconnected-(U27-NC-Pad1)") (class "Default")
      (node (ref "U27") (pin "1") (pinfunction "NC_1") (pintype "passive"))
    )
    (net (code "195") (name "unconnected-(U27-NC-Pad5)") (class "Default")
      (node (ref "U27") (pin "5") (pinfunction "NC_5") (pintype "passive"))
    )
    (net (code "196") (name "unconnected-(U27-NC-Pad8)") (class "Default")
      (node (ref "U27") (pin "8") (pinfunction "NC_8") (pintype "passive"))
    )
  )
)
